# harp_load_cells_v1_1.net
KiCad netlist of a schematic drawn in EAGLE
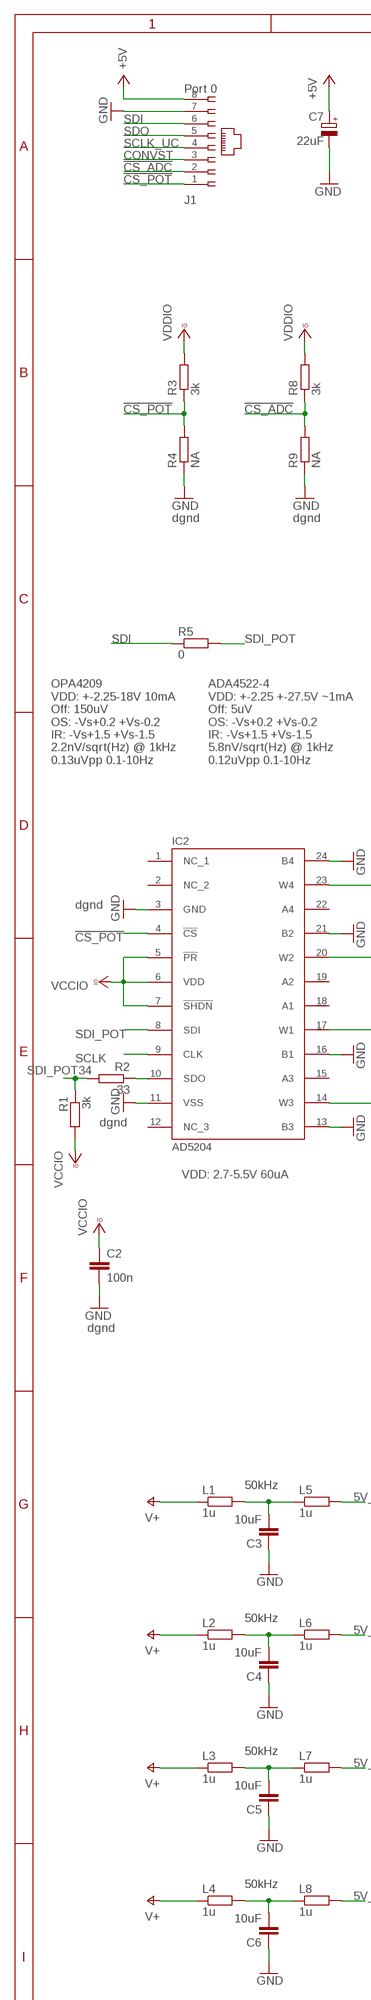
[diagram p0: schematic, sheet 1, part 1 of 2]
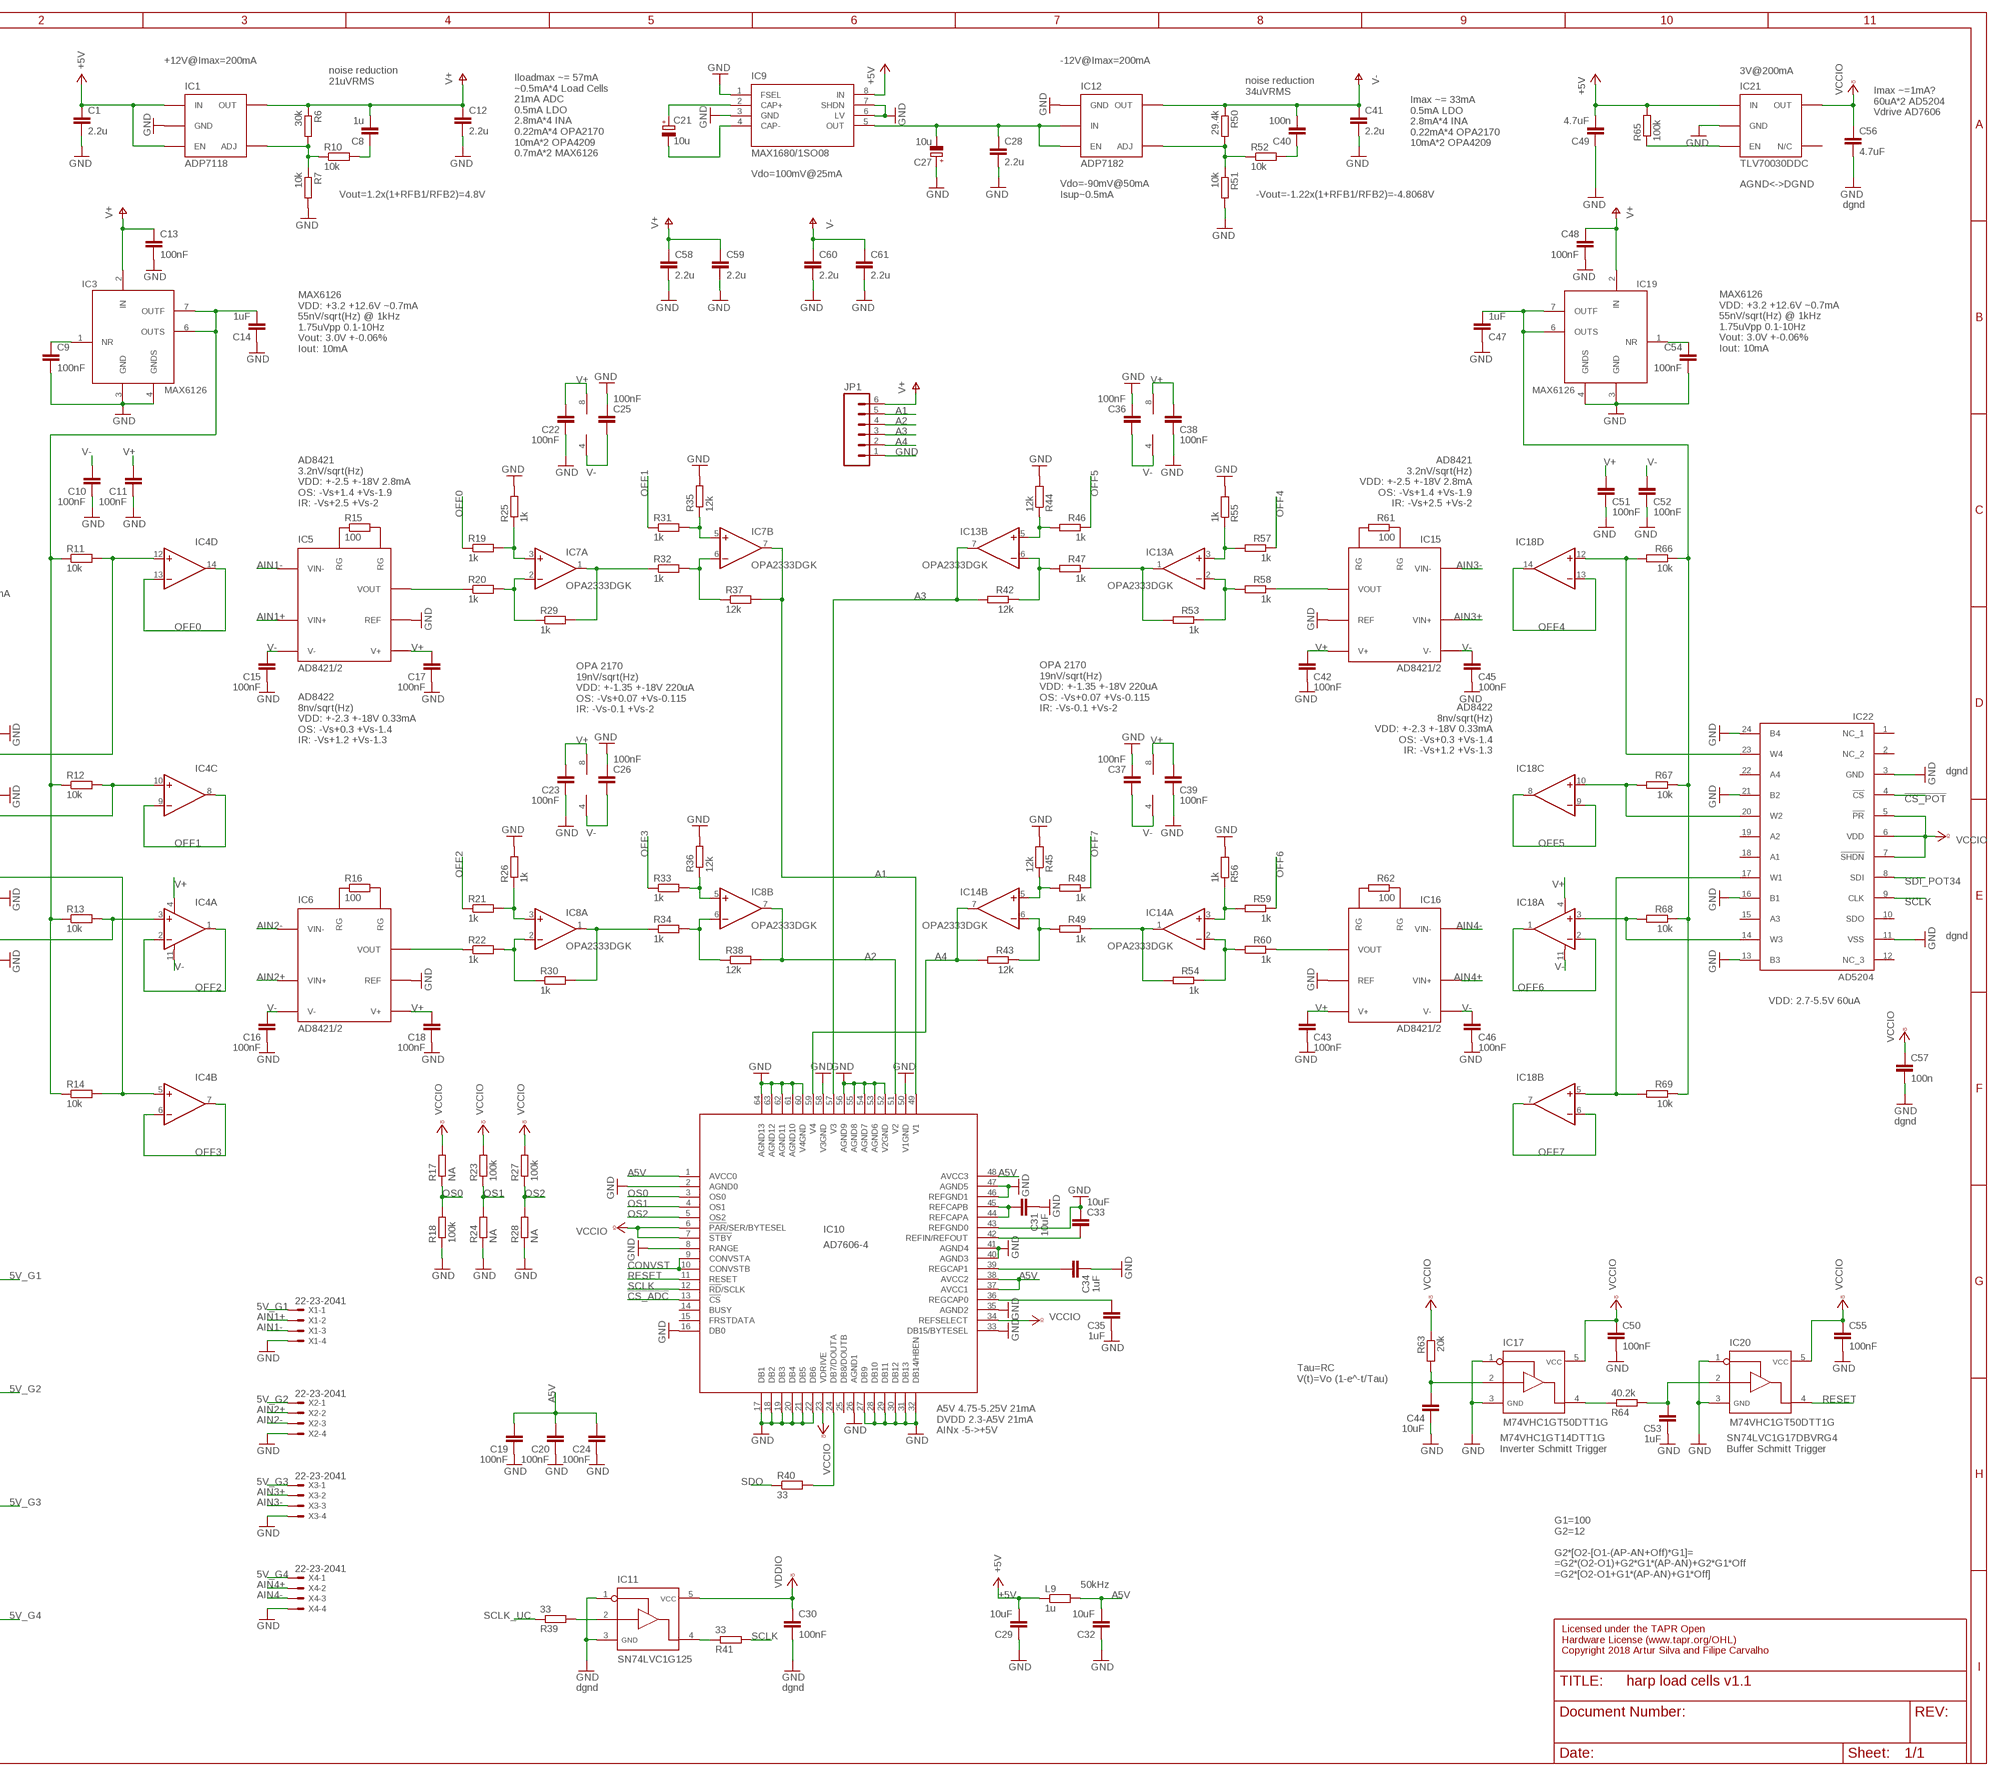
[diagram p1: schematic, sheet 1, part 2 of 2]

(export (version "E")
  (design (tool "Eeschema 10.0.6"))
  (components
    (comp (ref "C1")
      (value "2.2u")
      (footprint "eagle-import:C0603")
      (libsource (lib "eagle-import") (part "C-EUC0603"))
    )
    (comp (ref "C2")
      (value "100n")
      (footprint "eagle-import:C0402")
      (libsource (lib "eagle-import") (part "C-EUC0402"))
    )
    (comp (ref "C3")
      (value "10uF")
      (footprint "eagle-import:C0603")
      (libsource (lib "eagle-import") (part "C-EUC0603"))
    )
    (comp (ref "C4")
      (value "10uF")
      (footprint "eagle-import:C0603")
      (libsource (lib "eagle-import") (part "C-EUC0603"))
    )
    (comp (ref "C5")
      (value "10uF")
      (footprint "eagle-import:C0603")
      (libsource (lib "eagle-import") (part "C-EUC0603"))
    )
    (comp (ref "C6")
      (value "10uF")
      (footprint "eagle-import:C0603")
      (libsource (lib "eagle-import") (part "C-EUC0603"))
    )
    (comp (ref "C7")
      (value "22uF")
      (footprint "eagle-import:CAP_100UF_HAND")
      (libsource (lib "eagle-import") (part "CAP_100UFHAND"))
    )
    (comp (ref "C8")
      (value "1u")
      (footprint "eagle-import:C0402")
      (libsource (lib "eagle-import") (part "C-EUC0402"))
    )
    (comp (ref "C9")
      (value "100nF")
      (footprint "eagle-import:C0402")
      (libsource (lib "eagle-import") (part "C-EUC0402"))
    )
    (comp (ref "C10")
      (value "100nF")
      (footprint "eagle-import:C0402")
      (libsource (lib "eagle-import") (part "C-EUC0402"))
    )
    (comp (ref "C11")
      (value "100nF")
      (footprint "eagle-import:C0402")
      (libsource (lib "eagle-import") (part "C-EUC0402"))
    )
    (comp (ref "C12")
      (value "2.2u")
      (footprint "eagle-import:C0603")
      (libsource (lib "eagle-import") (part "C-EUC0603"))
    )
    (comp (ref "C13")
      (value "100nF")
      (footprint "eagle-import:C0402")
      (libsource (lib "eagle-import") (part "C-EUC0402"))
    )
    (comp (ref "C14")
      (value "1uF")
      (footprint "eagle-import:C0603")
      (libsource (lib "eagle-import") (part "C-EUC0603"))
    )
    (comp (ref "C15")
      (value "100nF")
      (footprint "eagle-import:C0402")
      (libsource (lib "eagle-import") (part "C-EUC0402"))
    )
    (comp (ref "C16")
      (value "100nF")
      (footprint "eagle-import:C0402")
      (libsource (lib "eagle-import") (part "C-EUC0402"))
    )
    (comp (ref "C17")
      (value "100nF")
      (footprint "eagle-import:C0402")
      (libsource (lib "eagle-import") (part "C-EUC0402"))
    )
    (comp (ref "C18")
      (value "100nF")
      (footprint "eagle-import:C0402")
      (libsource (lib "eagle-import") (part "C-EUC0402"))
    )
    (comp (ref "C19")
      (value "100nF")
      (footprint "eagle-import:C0402")
      (libsource (lib "eagle-import") (part "C-EUC0402"))
    )
    (comp (ref "C20")
      (value "100nF")
      (footprint "eagle-import:C0402")
      (libsource (lib "eagle-import") (part "C-EUC0402"))
    )
    (comp (ref "C21")
      (value "10u")
      (footprint "eagle-import:A_3216-18W")
      (libsource (lib "eagle-import") (part "CPOL-EUA/3216-18W"))
    )
    (comp (ref "C22")
      (value "100nF")
      (footprint "eagle-import:C0402")
      (libsource (lib "eagle-import") (part "C-EUC0402"))
    )
    (comp (ref "C23")
      (value "100nF")
      (footprint "eagle-import:C0402")
      (libsource (lib "eagle-import") (part "C-EUC0402"))
    )
    (comp (ref "C24")
      (value "100nF")
      (footprint "eagle-import:C0402")
      (libsource (lib "eagle-import") (part "C-EUC0402"))
    )
    (comp (ref "C25")
      (value "100nF")
      (footprint "eagle-import:C0402")
      (libsource (lib "eagle-import") (part "C-EUC0402"))
    )
    (comp (ref "C26")
      (value "100nF")
      (footprint "eagle-import:C0402")
      (libsource (lib "eagle-import") (part "C-EUC0402"))
    )
    (comp (ref "C27")
      (value "10u")
      (footprint "eagle-import:A_3216-18W")
      (libsource (lib "eagle-import") (part "CPOL-EUA/3216-18W"))
    )
    (comp (ref "C28")
      (value "2.2u")
      (footprint "eagle-import:C0603")
      (libsource (lib "eagle-import") (part "C-EUC0603"))
    )
    (comp (ref "C29")
      (value "10uF")
      (footprint "eagle-import:C0603")
      (libsource (lib "eagle-import") (part "C-EUC0603"))
    )
    (comp (ref "C30")
      (value "100nF")
      (footprint "eagle-import:C0402")
      (libsource (lib "eagle-import") (part "C-EUC0402"))
    )
    (comp (ref "C31")
      (value "10uF")
      (footprint "eagle-import:C0603")
      (libsource (lib "eagle-import") (part "C-EUC0603"))
    )
    (comp (ref "C32")
      (value "10uF")
      (footprint "eagle-import:C0603")
      (libsource (lib "eagle-import") (part "C-EUC0603"))
    )
    (comp (ref "C33")
      (value "10uF")
      (footprint "eagle-import:C0603")
      (libsource (lib "eagle-import") (part "C-EUC0603"))
    )
    (comp (ref "C34")
      (value "1uF")
      (footprint "eagle-import:C0402")
      (libsource (lib "eagle-import") (part "C-EUC0402"))
    )
    (comp (ref "C35")
      (value "1uF")
      (footprint "eagle-import:C0402")
      (libsource (lib "eagle-import") (part "C-EUC0402"))
    )
    (comp (ref "C36")
      (value "100nF")
      (footprint "eagle-import:C0402")
      (libsource (lib "eagle-import") (part "C-EUC0402"))
    )
    (comp (ref "C37")
      (value "100nF")
      (footprint "eagle-import:C0402")
      (libsource (lib "eagle-import") (part "C-EUC0402"))
    )
    (comp (ref "C38")
      (value "100nF")
      (footprint "eagle-import:C0402")
      (libsource (lib "eagle-import") (part "C-EUC0402"))
    )
    (comp (ref "C39")
      (value "100nF")
      (footprint "eagle-import:C0402")
      (libsource (lib "eagle-import") (part "C-EUC0402"))
    )
    (comp (ref "C40")
      (value "100n")
      (footprint "eagle-import:C0402")
      (libsource (lib "eagle-import") (part "C-EUC0402"))
    )
    (comp (ref "C41")
      (value "2.2u")
      (footprint "eagle-import:C0603")
      (libsource (lib "eagle-import") (part "C-EUC0603"))
    )
    (comp (ref "C42")
      (value "100nF")
      (footprint "eagle-import:C0402")
      (libsource (lib "eagle-import") (part "C-EUC0402"))
    )
    (comp (ref "C43")
      (value "100nF")
      (footprint "eagle-import:C0402")
      (libsource (lib "eagle-import") (part "C-EUC0402"))
    )
    (comp (ref "C44")
      (value "10uF")
      (footprint "eagle-import:C0603")
      (libsource (lib "eagle-import") (part "C-EUC0603"))
    )
    (comp (ref "C45")
      (value "100nF")
      (footprint "eagle-import:C0402")
      (libsource (lib "eagle-import") (part "C-EUC0402"))
    )
    (comp (ref "C46")
      (value "100nF")
      (footprint "eagle-import:C0402")
      (libsource (lib "eagle-import") (part "C-EUC0402"))
    )
    (comp (ref "C47")
      (value "1uF")
      (footprint "eagle-import:C0603")
      (libsource (lib "eagle-import") (part "C-EUC0603"))
    )
    (comp (ref "C48")
      (value "100nF")
      (footprint "eagle-import:C0402")
      (libsource (lib "eagle-import") (part "C-EUC0402"))
    )
    (comp (ref "C49")
      (value "4.7uF")
      (footprint "eagle-import:C0603")
      (libsource (lib "eagle-import") (part "C-EUC0603"))
    )
    (comp (ref "C50")
      (value "100nF")
      (footprint "eagle-import:C0402")
      (libsource (lib "eagle-import") (part "C-EUC0402"))
    )
    (comp (ref "C51")
      (value "100nF")
      (footprint "eagle-import:C0402")
      (libsource (lib "eagle-import") (part "C-EUC0402"))
    )
    (comp (ref "C52")
      (value "100nF")
      (footprint "eagle-import:C0402")
      (libsource (lib "eagle-import") (part "C-EUC0402"))
    )
    (comp (ref "C53")
      (value "1uF")
      (footprint "eagle-import:C0603")
      (libsource (lib "eagle-import") (part "C-EUC0603"))
    )
    (comp (ref "C54")
      (value "100nF")
      (footprint "eagle-import:C0402")
      (libsource (lib "eagle-import") (part "C-EUC0402"))
    )
    (comp (ref "C55")
      (value "100nF")
      (footprint "eagle-import:C0402")
      (libsource (lib "eagle-import") (part "C-EUC0402"))
    )
    (comp (ref "C56")
      (value "4.7uF")
      (footprint "eagle-import:C0603")
      (libsource (lib "eagle-import") (part "C-EUC0603"))
    )
    (comp (ref "C57")
      (value "100n")
      (footprint "eagle-import:C0402")
      (libsource (lib "eagle-import") (part "C-EUC0402"))
    )
    (comp (ref "C58")
      (value "2.2u")
      (footprint "eagle-import:C0603")
      (libsource (lib "eagle-import") (part "C-EUC0603"))
    )
    (comp (ref "C59")
      (value "2.2u")
      (footprint "eagle-import:C0603")
      (libsource (lib "eagle-import") (part "C-EUC0603"))
    )
    (comp (ref "C60")
      (value "2.2u")
      (footprint "eagle-import:C0603")
      (libsource (lib "eagle-import") (part "C-EUC0603"))
    )
    (comp (ref "C61")
      (value "2.2u")
      (footprint "eagle-import:C0603")
      (libsource (lib "eagle-import") (part "C-EUC0603"))
    )
    (comp (ref "IC1")
      (value "ADP7118")
      (footprint "eagle-import:TSOT23-5")
      (libsource (lib "eagle-import") (part "ADP7118"))
    )
    (comp (ref "IC2")
      (value "AD5204")
      (footprint "eagle-import:TSSOP-24")
      (libsource (lib "eagle-import") (part "AD5204"))
    )
    (comp (ref "IC3")
      (value "MAX6126")
      (footprint "eagle-import:SO08")
      (libsource (lib "eagle-import") (part "MAX6126"))
    )
    (comp (ref "IC4")
      (value "OPA4336T")
      (footprint "eagle-import:TSSOP-14")
      (libsource (lib "eagle-import") (part "OPA4336T"))
    )
    (comp (ref "IC5")
      (value "AD8421/2")
      (footprint "eagle-import:MSOP8")
      (libsource (lib "eagle-import") (part "AD8421/2"))
    )
    (comp (ref "IC6")
      (value "AD8421/2")
      (footprint "eagle-import:MSOP8")
      (libsource (lib "eagle-import") (part "AD8421/2"))
    )
    (comp (ref "IC7")
      (value "OPA2333DGK")
      (footprint "eagle-import:MSOP08")
      (libsource (lib "eagle-import") (part "OPA2333DGK"))
    )
    (comp (ref "IC8")
      (value "OPA2333DGK")
      (footprint "eagle-import:MSOP08")
      (libsource (lib "eagle-import") (part "OPA2333DGK"))
    )
    (comp (ref "IC9")
      (value "MAX1680/1SO08")
      (footprint "eagle-import:SO08")
      (libsource (lib "eagle-import") (part "MAX1680/1SO08"))
    )
    (comp (ref "IC10")
      (value "AD7606-4")
      (footprint "eagle-import:LQFP-64")
      (libsource (lib "eagle-import") (part "AD7606-4"))
    )
    (comp (ref "IC11")
      (value "SN74LVC1G125")
      (footprint "eagle-import:SOT23-5")
      (libsource (lib "eagle-import") (part "SN74LVC1G125"))
    )
    (comp (ref "IC12")
      (value "ADP7182")
      (footprint "eagle-import:TSOT23-5")
      (libsource (lib "eagle-import") (part "ADP7182"))
    )
    (comp (ref "IC13")
      (value "OPA2333DGK")
      (footprint "eagle-import:MSOP08")
      (libsource (lib "eagle-import") (part "OPA2333DGK"))
    )
    (comp (ref "IC14")
      (value "OPA2333DGK")
      (footprint "eagle-import:MSOP08")
      (libsource (lib "eagle-import") (part "OPA2333DGK"))
    )
    (comp (ref "IC15")
      (value "AD8421/2")
      (footprint "eagle-import:MSOP8")
      (libsource (lib "eagle-import") (part "AD8421/2"))
    )
    (comp (ref "IC16")
      (value "AD8421/2")
      (footprint "eagle-import:MSOP8")
      (libsource (lib "eagle-import") (part "AD8421/2"))
    )
    (comp (ref "IC17")
      (value "M74VHC1GT50DTT1G")
      (footprint "eagle-import:SOT23-5")
      (libsource (lib "eagle-import") (part "SN74LVC1G125"))
    )
    (comp (ref "IC18")
      (value "OPA4336T")
      (footprint "eagle-import:TSSOP-14")
      (libsource (lib "eagle-import") (part "OPA4336T"))
    )
    (comp (ref "IC19")
      (value "MAX6126")
      (footprint "eagle-import:SO08")
      (libsource (lib "eagle-import") (part "MAX6126"))
    )
    (comp (ref "IC20")
      (value "M74VHC1GT50DTT1G")
      (footprint "eagle-import:SOT23-5")
      (libsource (lib "eagle-import") (part "SN74LVC1G125"))
    )
    (comp (ref "IC21")
      (value "TLV70030DDC")
      (footprint "eagle-import:TSOT23-5")
      (libsource (lib "eagle-import") (part "TLV700XX"))
    )
    (comp (ref "IC22")
      (value "AD5204")
      (footprint "eagle-import:TSSOP-24")
      (libsource (lib "eagle-import") (part "AD5204"))
    )
    (comp (ref "J1")
      (value "Port 0")
      (footprint "eagle-import:520426-4")
      (libsource (lib "eagle-import") (part "520426-4"))
    )
    (comp (ref "JP1")
      (value "M06NO_SILK")
      (footprint "eagle-import:1X06_NO_SILK")
      (libsource (lib "eagle-import") (part "M06NO_SILK"))
    )
    (comp (ref "L1")
      (value "1u")
      (footprint "eagle-import:R0402")
      (libsource (lib "eagle-import") (part "R-EU_R0402"))
    )
    (comp (ref "L2")
      (value "1u")
      (footprint "eagle-import:R0402")
      (libsource (lib "eagle-import") (part "R-EU_R0402"))
    )
    (comp (ref "L3")
      (value "1u")
      (footprint "eagle-import:R0402")
      (libsource (lib "eagle-import") (part "R-EU_R0402"))
    )
    (comp (ref "L4")
      (value "1u")
      (footprint "eagle-import:R0402")
      (libsource (lib "eagle-import") (part "R-EU_R0402"))
    )
    (comp (ref "L5")
      (value "1u")
      (footprint "eagle-import:R0402")
      (libsource (lib "eagle-import") (part "R-EU_R0402"))
    )
    (comp (ref "L6")
      (value "1u")
      (footprint "eagle-import:R0402")
      (libsource (lib "eagle-import") (part "R-EU_R0402"))
    )
    (comp (ref "L7")
      (value "1u")
      (footprint "eagle-import:R0402")
      (libsource (lib "eagle-import") (part "R-EU_R0402"))
    )
    (comp (ref "L8")
      (value "1u")
      (footprint "eagle-import:R0402")
      (libsource (lib "eagle-import") (part "R-EU_R0402"))
    )
    (comp (ref "L9")
      (value "1u")
      (footprint "eagle-import:R0402")
      (libsource (lib "eagle-import") (part "R-EU_R0402"))
    )
    (comp (ref "R1")
      (value "3k")
      (footprint "eagle-import:R0402")
      (libsource (lib "eagle-import") (part "R-EU_R0402"))
    )
    (comp (ref "R2")
      (value "33")
      (footprint "eagle-import:R0402")
      (libsource (lib "eagle-import") (part "R-EU_R0402"))
    )
    (comp (ref "R3")
      (value "3k")
      (footprint "eagle-import:R0402")
      (libsource (lib "eagle-import") (part "R-EU_R0402"))
    )
    (comp (ref "R4")
      (value "NA")
      (footprint "eagle-import:R0402")
      (libsource (lib "eagle-import") (part "R-EU_R0402"))
    )
    (comp (ref "R5")
      (value "0")
      (footprint "eagle-import:R0402")
      (libsource (lib "eagle-import") (part "R-EU_R0402"))
    )
    (comp (ref "R6")
      (value "30k")
      (footprint "eagle-import:R0402")
      (libsource (lib "eagle-import") (part "R-EU_R0402"))
    )
    (comp (ref "R7")
      (value "10k")
      (footprint "eagle-import:R0402")
      (libsource (lib "eagle-import") (part "R-EU_R0402"))
    )
    (comp (ref "R8")
      (value "3k")
      (footprint "eagle-import:R0402")
      (libsource (lib "eagle-import") (part "R-EU_R0402"))
    )
    (comp (ref "R9")
      (value "NA")
      (footprint "eagle-import:R0402")
      (libsource (lib "eagle-import") (part "R-EU_R0402"))
    )
    (comp (ref "R10")
      (value "10k")
      (footprint "eagle-import:R0402")
      (libsource (lib "eagle-import") (part "R-EU_R0402"))
    )
    (comp (ref "R11")
      (value "10k")
      (footprint "eagle-import:R0402")
      (libsource (lib "eagle-import") (part "R-EU_R0402"))
    )
    (comp (ref "R12")
      (value "10k")
      (footprint "eagle-import:R0402")
      (libsource (lib "eagle-import") (part "R-EU_R0402"))
    )
    (comp (ref "R13")
      (value "10k")
      (footprint "eagle-import:R0402")
      (libsource (lib "eagle-import") (part "R-EU_R0402"))
    )
    (comp (ref "R14")
      (value "10k")
      (footprint "eagle-import:R0402")
      (libsource (lib "eagle-import") (part "R-EU_R0402"))
    )
    (comp (ref "R15")
      (value "100")
      (footprint "eagle-import:R0402")
      (libsource (lib "eagle-import") (part "R-EU_R0402"))
    )
    (comp (ref "R16")
      (value "100")
      (footprint "eagle-import:R0402")
      (libsource (lib "eagle-import") (part "R-EU_R0402"))
    )
    (comp (ref "R17")
      (value "NA")
      (footprint "eagle-import:R0402")
      (libsource (lib "eagle-import") (part "R-EU_R0402"))
    )
    (comp (ref "R18")
      (value "100k")
      (footprint "eagle-import:R0402")
      (libsource (lib "eagle-import") (part "R-EU_R0402"))
    )
    (comp (ref "R19")
      (value "1k")
      (footprint "eagle-import:R0402")
      (libsource (lib "eagle-import") (part "R-EU_R0402"))
    )
    (comp (ref "R20")
      (value "1k")
      (footprint "eagle-import:R0402")
      (libsource (lib "eagle-import") (part "R-EU_R0402"))
    )
    (comp (ref "R21")
      (value "1k")
      (footprint "eagle-import:R0402")
      (libsource (lib "eagle-import") (part "R-EU_R0402"))
    )
    (comp (ref "R22")
      (value "1k")
      (footprint "eagle-import:R0402")
      (libsource (lib "eagle-import") (part "R-EU_R0402"))
    )
    (comp (ref "R23")
      (value "100k")
      (footprint "eagle-import:R0402")
      (libsource (lib "eagle-import") (part "R-EU_R0402"))
    )
    (comp (ref "R24")
      (value "NA")
      (footprint "eagle-import:R0402")
      (libsource (lib "eagle-import") (part "R-EU_R0402"))
    )
    (comp (ref "R25")
      (value "1k")
      (footprint "eagle-import:R0402")
      (libsource (lib "eagle-import") (part "R-EU_R0402"))
    )
    (comp (ref "R26")
      (value "1k")
      (footprint "eagle-import:R0402")
      (libsource (lib "eagle-import") (part "R-EU_R0402"))
    )
    (comp (ref "R27")
      (value "100k")
      (footprint "eagle-import:R0402")
      (libsource (lib "eagle-import") (part "R-EU_R0402"))
    )
    (comp (ref "R28")
      (value "NA")
      (footprint "eagle-import:R0402")
      (libsource (lib "eagle-import") (part "R-EU_R0402"))
    )
    (comp (ref "R29")
      (value "1k")
      (footprint "eagle-import:R0402")
      (libsource (lib "eagle-import") (part "R-EU_R0402"))
    )
    (comp (ref "R30")
      (value "1k")
      (footprint "eagle-import:R0402")
      (libsource (lib "eagle-import") (part "R-EU_R0402"))
    )
    (comp (ref "R31")
      (value "1k")
      (footprint "eagle-import:R0402")
      (libsource (lib "eagle-import") (part "R-EU_R0402"))
    )
    (comp (ref "R32")
      (value "1k")
      (footprint "eagle-import:R0402")
      (libsource (lib "eagle-import") (part "R-EU_R0402"))
    )
    (comp (ref "R33")
      (value "1k")
      (footprint "eagle-import:R0402")
      (libsource (lib "eagle-import") (part "R-EU_R0402"))
    )
    (comp (ref "R34")
      (value "1k")
      (footprint "eagle-import:R0402")
      (libsource (lib "eagle-import") (part "R-EU_R0402"))
    )
    (comp (ref "R35")
      (value "12k")
      (footprint "eagle-import:R0402")
      (libsource (lib "eagle-import") (part "R-EU_R0402"))
    )
    (comp (ref "R36")
      (value "12k")
      (footprint "eagle-import:R0402")
      (libsource (lib "eagle-import") (part "R-EU_R0402"))
    )
    (comp (ref "R37")
      (value "12k")
      (footprint "eagle-import:R0402")
      (libsource (lib "eagle-import") (part "R-EU_R0402"))
    )
    (comp (ref "R38")
      (value "12k")
      (footprint "eagle-import:R0402")
      (libsource (lib "eagle-import") (part "R-EU_R0402"))
    )
    (comp (ref "R39")
      (value "33")
      (footprint "eagle-import:R0402")
      (libsource (lib "eagle-import") (part "R-EU_R0402"))
    )
    (comp (ref "R40")
      (value "33")
      (footprint "eagle-import:R0402")
      (libsource (lib "eagle-import") (part "R-EU_R0402"))
    )
    (comp (ref "R41")
      (value "33")
      (footprint "eagle-import:R0402")
      (libsource (lib "eagle-import") (part "R-EU_R0402"))
    )
    (comp (ref "R42")
      (value "12k")
      (footprint "eagle-import:R0402")
      (libsource (lib "eagle-import") (part "R-EU_R0402"))
    )
    (comp (ref "R43")
      (value "12k")
      (footprint "eagle-import:R0402")
      (libsource (lib "eagle-import") (part "R-EU_R0402"))
    )
    (comp (ref "R44")
      (value "12k")
      (footprint "eagle-import:R0402")
      (libsource (lib "eagle-import") (part "R-EU_R0402"))
    )
    (comp (ref "R45")
      (value "12k")
      (footprint "eagle-import:R0402")
      (libsource (lib "eagle-import") (part "R-EU_R0402"))
    )
    (comp (ref "R46")
      (value "1k")
      (footprint "eagle-import:R0402")
      (libsource (lib "eagle-import") (part "R-EU_R0402"))
    )
    (comp (ref "R47")
      (value "1k")
      (footprint "eagle-import:R0402")
      (libsource (lib "eagle-import") (part "R-EU_R0402"))
    )
    (comp (ref "R48")
      (value "1k")
      (footprint "eagle-import:R0402")
      (libsource (lib "eagle-import") (part "R-EU_R0402"))
    )
    (comp (ref "R49")
      (value "1k")
      (footprint "eagle-import:R0402")
      (libsource (lib "eagle-import") (part "R-EU_R0402"))
    )
    (comp (ref "R50")
      (value "29.4k")
      (footprint "eagle-import:R0402")
      (libsource (lib "eagle-import") (part "R-EU_R0402"))
    )
    (comp (ref "R51")
      (value "10k")
      (footprint "eagle-import:R0402")
      (libsource (lib "eagle-import") (part "R-EU_R0402"))
    )
    (comp (ref "R52")
      (value "10k")
      (footprint "eagle-import:R0402")
      (libsource (lib "eagle-import") (part "R-EU_R0402"))
    )
    (comp (ref "R53")
      (value "1k")
      (footprint "eagle-import:R0402")
      (libsource (lib "eagle-import") (part "R-EU_R0402"))
    )
    (comp (ref "R54")
      (value "1k")
      (footprint "eagle-import:R0402")
      (libsource (lib "eagle-import") (part "R-EU_R0402"))
    )
    (comp (ref "R55")
      (value "1k")
      (footprint "eagle-import:R0402")
      (libsource (lib "eagle-import") (part "R-EU_R0402"))
    )
    (comp (ref "R56")
      (value "1k")
      (footprint "eagle-import:R0402")
      (libsource (lib "eagle-import") (part "R-EU_R0402"))
    )
    (comp (ref "R57")
      (value "1k")
      (footprint "eagle-import:R0402")
      (libsource (lib "eagle-import") (part "R-EU_R0402"))
    )
    (comp (ref "R58")
      (value "1k")
      (footprint "eagle-import:R0402")
      (libsource (lib "eagle-import") (part "R-EU_R0402"))
    )
    (comp (ref "R59")
      (value "1k")
      (footprint "eagle-import:R0402")
      (libsource (lib "eagle-import") (part "R-EU_R0402"))
    )
    (comp (ref "R60")
      (value "1k")
      (footprint "eagle-import:R0402")
      (libsource (lib "eagle-import") (part "R-EU_R0402"))
    )
    (comp (ref "R61")
      (value "100")
      (footprint "eagle-import:R0402")
      (libsource (lib "eagle-import") (part "R-EU_R0402"))
    )
    (comp (ref "R62")
      (value "100")
      (footprint "eagle-import:R0402")
      (libsource (lib "eagle-import") (part "R-EU_R0402"))
    )
    (comp (ref "R63")
      (value "20k")
      (footprint "eagle-import:R0402")
      (libsource (lib "eagle-import") (part "R-EU_R0402"))
    )
    (comp (ref "R64")
      (value "40.2k")
      (footprint "eagle-import:R0402")
      (libsource (lib "eagle-import") (part "R-EU_R0402"))
    )
    (comp (ref "R65")
      (value "100k")
      (footprint "eagle-import:R0402")
      (libsource (lib "eagle-import") (part "R-EU_R0402"))
    )
    (comp (ref "R66")
      (value "10k")
      (footprint "eagle-import:R0402")
      (libsource (lib "eagle-import") (part "R-EU_R0402"))
    )
    (comp (ref "R67")
      (value "10k")
      (footprint "eagle-import:R0402")
      (libsource (lib "eagle-import") (part "R-EU_R0402"))
    )
    (comp (ref "R68")
      (value "10k")
      (footprint "eagle-import:R0402")
      (libsource (lib "eagle-import") (part "R-EU_R0402"))
    )
    (comp (ref "R69")
      (value "10k")
      (footprint "eagle-import:R0402")
      (libsource (lib "eagle-import") (part "R-EU_R0402"))
    )
    (comp (ref "X1")
      (value "22-23-2041")
      (footprint "eagle-import:22-23-2041")
      (fields (field (name "MF") "MOLEX"))
      (libsource (lib "eagle-import") (part "22-23-2041"))
    )
    (comp (ref "X2")
      (value "22-23-2041")
      (footprint "eagle-import:22-23-2041")
      (fields (field (name "MF") "MOLEX"))
      (libsource (lib "eagle-import") (part "22-23-2041"))
    )
    (comp (ref "X3")
      (value "22-23-2041")
      (footprint "eagle-import:22-23-2041")
      (fields (field (name "MF") "MOLEX"))
      (libsource (lib "eagle-import") (part "22-23-2041"))
    )
    (comp (ref "X4")
      (value "22-23-2041")
      (footprint "eagle-import:22-23-2041")
      (fields (field (name "MF") "MOLEX"))
      (libsource (lib "eagle-import") (part "22-23-2041"))
    )
  )
  (nets
    (net (code "1") (name "+5V") (class "Default")
      (node (ref "C1") (pin "1") (pinfunction "1_1") (pintype "passive"))
      (node (ref "C29") (pin "2") (pinfunction "2_2") (pintype "passive"))
      (node (ref "C49") (pin "2") (pinfunction "2_2") (pintype "passive"))
      (node (ref "C7") (pin "+") (pinfunction "+_+") (pintype "passive"))
      (node (ref "IC1") (pin "1") (pinfunction "IN_1") (pintype "bidirectional"))
      (node (ref "IC1") (pin "3") (pinfunction "EN_3") (pintype "bidirectional"))
      (node (ref "IC21") (pin "1") (pinfunction "IN_1") (pintype "bidirectional"))
      (node (ref "IC9") (pin "8") (pinfunction "IN_8") (pintype "bidirectional"))
      (node (ref "J1") (pin "8") (pinfunction "8_8") (pintype "passive"))
      (node (ref "L9") (pin "1") (pinfunction "1_1") (pintype "passive"))
      (node (ref "R65") (pin "2") (pinfunction "2_2") (pintype "passive"))
    )
    (net (code "2") (name "/5V_G1") (class "Default")
      (node (ref "L5") (pin "2") (pinfunction "2_2") (pintype "passive"))
      (node (ref "X1") (pin "1") (pinfunction "S_1") (pintype "passive"))
    )
    (net (code "3") (name "/5V_G2") (class "Default")
      (node (ref "L6") (pin "2") (pinfunction "2_2") (pintype "passive"))
      (node (ref "X2") (pin "1") (pinfunction "S_1") (pintype "passive"))
    )
    (net (code "4") (name "/5V_G3") (class "Default")
      (node (ref "L7") (pin "2") (pinfunction "2_2") (pintype "passive"))
      (node (ref "X3") (pin "1") (pinfunction "S_1") (pintype "passive"))
    )
    (net (code "5") (name "/5V_G4") (class "Default")
      (node (ref "L8") (pin "2") (pinfunction "2_2") (pintype "passive"))
      (node (ref "X4") (pin "1") (pinfunction "S_1") (pintype "passive"))
    )
    (net (code "6") (name "/A1") (class "Default")
      (node (ref "IC10") (pin "49") (pinfunction "V1_49") (pintype "bidirectional"))
      (node (ref "IC7") (pin "7") (pinfunction "OUT_7") (pintype "output"))
      (node (ref "JP1") (pin "5") (pinfunction "5_5") (pintype "passive"))
      (node (ref "R37") (pin "2") (pinfunction "2_2") (pintype "passive"))
    )
    (net (code "7") (name "/A2") (class "Default")
      (node (ref "IC10") (pin "51") (pinfunction "V2_51") (pintype "bidirectional"))
      (node (ref "IC8") (pin "7") (pinfunction "OUT_7") (pintype "output"))
      (node (ref "JP1") (pin "4") (pinfunction "4_4") (pintype "passive"))
      (node (ref "R38") (pin "2") (pinfunction "2_2") (pintype "passive"))
    )
    (net (code "8") (name "/A3") (class "Default")
      (node (ref "IC10") (pin "57") (pinfunction "V3_57") (pintype "bidirectional"))
      (node (ref "IC13") (pin "7") (pinfunction "OUT_7") (pintype "output"))
      (node (ref "JP1") (pin "3") (pinfunction "3_3") (pintype "passive"))
      (node (ref "R42") (pin "2") (pinfunction "2_2") (pintype "passive"))
    )
    (net (code "9") (name "/A4") (class "Default")
      (node (ref "IC10") (pin "59") (pinfunction "V4_59") (pintype "bidirectional"))
      (node (ref "IC14") (pin "7") (pinfunction "OUT_7") (pintype "output"))
      (node (ref "JP1") (pin "2") (pinfunction "2_2") (pintype "passive"))
      (node (ref "R43") (pin "2") (pinfunction "2_2") (pintype "passive"))
    )
    (net (code "10") (name "/A5V") (class "Default")
      (node (ref "C19") (pin "2") (pinfunction "2_2") (pintype "passive"))
      (node (ref "C20") (pin "2") (pinfunction "2_2") (pintype "passive"))
      (node (ref "C24") (pin "2") (pinfunction "2_2") (pintype "passive"))
      (node (ref "C32") (pin "2") (pinfunction "2_2") (pintype "passive"))
      (node (ref "IC10") (pin "1") (pinfunction "AVCC0_1") (pintype "bidirectional"))
      (node (ref "IC10") (pin "37") (pinfunction "AVCC1_37") (pintype "bidirectional"))
      (node (ref "IC10") (pin "38") (pinfunction "AVCC2_38") (pintype "bidirectional"))
      (node (ref "IC10") (pin "48") (pinfunction "AVCC3_48") (pintype "bidirectional"))
      (node (ref "L9") (pin "2") (pinfunction "2_2") (pintype "passive"))
    )
    (net (code "11") (name "/AIN1+") (class "Default")
      (node (ref "IC5") (pin "P$4") (pinfunction "VIN+_P$4") (pintype "bidirectional"))
      (node (ref "X1") (pin "2") (pinfunction "S_2") (pintype "passive"))
    )
    (net (code "12") (name "/AIN1-") (class "Default")
      (node (ref "IC5") (pin "P$1") (pinfunction "VIN-_P$1") (pintype "bidirectional"))
      (node (ref "X1") (pin "3") (pinfunction "S_3") (pintype "passive"))
    )
    (net (code "13") (name "/AIN2+") (class "Default")
      (node (ref "IC6") (pin "P$4") (pinfunction "VIN+_P$4") (pintype "bidirectional"))
      (node (ref "X2") (pin "2") (pinfunction "S_2") (pintype "passive"))
    )
    (net (code "14") (name "/AIN2-") (class "Default")
      (node (ref "IC6") (pin "P$1") (pinfunction "VIN-_P$1") (pintype "bidirectional"))
      (node (ref "X2") (pin "3") (pinfunction "S_3") (pintype "passive"))
    )
    (net (code "15") (name "/AIN3+") (class "Default")
      (node (ref "IC15") (pin "P$4") (pinfunction "VIN+_P$4") (pintype "bidirectional"))
      (node (ref "X3") (pin "2") (pinfunction "S_2") (pintype "passive"))
    )
    (net (code "16") (name "/AIN3-") (class "Default")
      (node (ref "IC15") (pin "P$1") (pinfunction "VIN-_P$1") (pintype "bidirectional"))
      (node (ref "X3") (pin "3") (pinfunction "S_3") (pintype "passive"))
    )
    (net (code "17") (name "/AIN4+") (class "Default")
      (node (ref "IC16") (pin "P$4") (pinfunction "VIN+_P$4") (pintype "bidirectional"))
      (node (ref "X4") (pin "2") (pinfunction "S_2") (pintype "passive"))
    )
    (net (code "18") (name "/AIN4-") (class "Default")
      (node (ref "IC16") (pin "P$1") (pinfunction "VIN-_P$1") (pintype "bidirectional"))
      (node (ref "X4") (pin "3") (pinfunction "S_3") (pintype "passive"))
    )
    (net (code "19") (name "/CONVST") (class "Default")
      (node (ref "IC10") (pin "10") (pinfunction "CONVSTB_10") (pintype "bidirectional"))
      (node (ref "IC10") (pin "9") (pinfunction "CONVSTA_9") (pintype "bidirectional"))
      (node (ref "J1") (pin "3") (pinfunction "3_3") (pintype "passive"))
    )
    (net (code "20") (name "/OFF0") (class "Default")
      (node (ref "IC4") (pin "13") (pinfunction "-IN_13") (pintype "input"))
      (node (ref "IC4") (pin "14") (pinfunction "OUT_14") (pintype "output"))
      (node (ref "R19") (pin "1") (pinfunction "1_1") (pintype "passive"))
    )
    (net (code "21") (name "/OFF1") (class "Default")
      (node (ref "IC4") (pin "8") (pinfunction "OUT_8") (pintype "output"))
      (node (ref "IC4") (pin "9") (pinfunction "-IN_9") (pintype "input"))
      (node (ref "R31") (pin "1") (pinfunction "1_1") (pintype "passive"))
    )
    (net (code "22") (name "/OFF2") (class "Default")
      (node (ref "IC4") (pin "1") (pinfunction "OUT_1") (pintype "output"))
      (node (ref "IC4") (pin "2") (pinfunction "-IN_2") (pintype "input"))
      (node (ref "R21") (pin "1") (pinfunction "1_1") (pintype "passive"))
    )
    (net (code "23") (name "/OFF3") (class "Default")
      (node (ref "IC4") (pin "6") (pinfunction "-IN_6") (pintype "input"))
      (node (ref "IC4") (pin "7") (pinfunction "OUT_7") (pintype "output"))
      (node (ref "R33") (pin "1") (pinfunction "1_1") (pintype "passive"))
    )
    (net (code "24") (name "/OFF4") (class "Default")
      (node (ref "IC18") (pin "13") (pinfunction "-IN_13") (pintype "input"))
      (node (ref "IC18") (pin "14") (pinfunction "OUT_14") (pintype "output"))
      (node (ref "R57") (pin "1") (pinfunction "1_1") (pintype "passive"))
    )
    (net (code "25") (name "/OFF5") (class "Default")
      (node (ref "IC18") (pin "8") (pinfunction "OUT_8") (pintype "output"))
      (node (ref "IC18") (pin "9") (pinfunction "-IN_9") (pintype "input"))
      (node (ref "R46") (pin "1") (pinfunction "1_1") (pintype "passive"))
    )
    (net (code "26") (name "/OFF6") (class "Default")
      (node (ref "IC18") (pin "1") (pinfunction "OUT_1") (pintype "output"))
      (node (ref "IC18") (pin "2") (pinfunction "-IN_2") (pintype "input"))
      (node (ref "R59") (pin "1") (pinfunction "1_1") (pintype "passive"))
    )
    (net (code "27") (name "/OFF7") (class "Default")
      (node (ref "IC18") (pin "6") (pinfunction "-IN_6") (pintype "input"))
      (node (ref "IC18") (pin "7") (pinfunction "OUT_7") (pintype "output"))
      (node (ref "R48") (pin "1") (pinfunction "1_1") (pintype "passive"))
    )
    (net (code "28") (name "/OS0") (class "Default")
      (node (ref "IC10") (pin "3") (pinfunction "OS0_3") (pintype "bidirectional"))
      (node (ref "R17") (pin "1") (pinfunction "1_1") (pintype "passive"))
      (node (ref "R18") (pin "2") (pinfunction "2_2") (pintype "passive"))
    )
    (net (code "29") (name "/OS1") (class "Default")
      (node (ref "IC10") (pin "4") (pinfunction "OS1_4") (pintype "bidirectional"))
      (node (ref "R23") (pin "1") (pinfunction "1_1") (pintype "passive"))
      (node (ref "R24") (pin "2") (pinfunction "2_2") (pintype "passive"))
    )
    (net (code "30") (name "/OS2") (class "Default")
      (node (ref "IC10") (pin "5") (pinfunction "OS2_5") (pintype "bidirectional"))
      (node (ref "R27") (pin "1") (pinfunction "1_1") (pintype "passive"))
      (node (ref "R28") (pin "2") (pinfunction "2_2") (pintype "passive"))
    )
    (net (code "31") (name "/RESET") (class "Default")
      (node (ref "IC10") (pin "11") (pinfunction "RESET_11") (pintype "bidirectional"))
      (node (ref "IC20") (pin "4") (pinfunction "P$4_4") (pintype "bidirectional"))
    )
    (net (code "32") (name "/SCLK") (class "Default")
      (node (ref "IC10") (pin "12") (pinfunction "~{RD}/SCLK_12") (pintype "bidirectional"))
      (node (ref "IC2") (pin "9") (pinfunction "CLK_9") (pintype "bidirectional"))
      (node (ref "IC22") (pin "9") (pinfunction "CLK_9") (pintype "bidirectional"))
      (node (ref "R41") (pin "2") (pinfunction "2_2") (pintype "passive"))
    )
    (net (code "33") (name "/SCLK_UC") (class "Default")
      (node (ref "J1") (pin "4") (pinfunction "4_4") (pintype "passive"))
      (node (ref "R39") (pin "1") (pinfunction "1_1") (pintype "passive"))
    )
    (net (code "34") (name "/SDI") (class "Default")
      (node (ref "J1") (pin "6") (pinfunction "6_6") (pintype "passive"))
      (node (ref "R5") (pin "1") (pinfunction "1_1") (pintype "passive"))
    )
    (net (code "35") (name "/SDI_POT") (class "Default")
      (node (ref "IC2") (pin "8") (pinfunction "SDI_8") (pintype "bidirectional"))
      (node (ref "R5") (pin "2") (pinfunction "2_2") (pintype "passive"))
    )
    (net (code "36") (name "/SDI_POT34") (class "Default")
      (node (ref "IC22") (pin "8") (pinfunction "SDI_8") (pintype "bidirectional"))
      (node (ref "R1") (pin "1") (pinfunction "1_1") (pintype "passive"))
      (node (ref "R2") (pin "2") (pinfunction "2_2") (pintype "passive"))
    )
    (net (code "37") (name "/SDO") (class "Default")
      (node (ref "J1") (pin "5") (pinfunction "5_5") (pintype "passive"))
      (node (ref "R40") (pin "1") (pinfunction "1_1") (pintype "passive"))
    )
    (net (code "38") (name "/~{CS_ADC}") (class "Default")
      (node (ref "IC10") (pin "13") (pinfunction "~{CS}_13") (pintype "input"))
      (node (ref "J1") (pin "2") (pinfunction "2_2") (pintype "passive"))
      (node (ref "R8") (pin "1") (pinfunction "1_1") (pintype "passive"))
      (node (ref "R9") (pin "2") (pinfunction "2_2") (pintype "passive"))
    )
    (net (code "39") (name "/~{CS_POT}") (class "Default")
      (node (ref "IC2") (pin "4") (pinfunction "~{CS}_4") (pintype "bidirectional"))
      (node (ref "IC22") (pin "4") (pinfunction "~{CS}_4") (pintype "bidirectional"))
      (node (ref "J1") (pin "1") (pinfunction "1_1") (pintype "passive"))
      (node (ref "R3") (pin "1") (pinfunction "1_1") (pintype "passive"))
      (node (ref "R4") (pin "2") (pinfunction "2_2") (pintype "passive"))
    )
    (net (code "40") (name "GND") (class "Default")
      (node (ref "C1") (pin "2") (pinfunction "2_2") (pintype "passive"))
      (node (ref "C10") (pin "1") (pinfunction "1_1") (pintype "passive"))
      (node (ref "C11") (pin "1") (pinfunction "1_1") (pintype "passive"))
      (node (ref "C12") (pin "2") (pinfunction "2_2") (pintype "passive"))
      (node (ref "C13") (pin "2") (pinfunction "2_2") (pintype "passive"))
      (node (ref "C14") (pin "1") (pinfunction "1_1") (pintype "passive"))
      (node (ref "C15") (pin "1") (pinfunction "1_1") (pintype "passive"))
      (node (ref "C16") (pin "1") (pinfunction "1_1") (pintype "passive"))
      (node (ref "C17") (pin "1") (pinfunction "1_1") (pintype "passive"))
      (node (ref "C18") (pin "1") (pinfunction "1_1") (pintype "passive"))
      (node (ref "C19") (pin "1") (pinfunction "1_1") (pintype "passive"))
      (node (ref "C2") (pin "2") (pinfunction "2_2") (pintype "passive"))
      (node (ref "C20") (pin "1") (pinfunction "1_1") (pintype "passive"))
      (node (ref "C22") (pin "1") (pinfunction "1_1") (pintype "passive"))
      (node (ref "C23") (pin "1") (pinfunction "1_1") (pintype "passive"))
      (node (ref "C24") (pin "1") (pinfunction "1_1") (pintype "passive"))
      (node (ref "C25") (pin "1") (pinfunction "1_1") (pintype "passive"))
      (node (ref "C26") (pin "1") (pinfunction "1_1") (pintype "passive"))
      (node (ref "C27") (pin "+") (pinfunction "+_+") (pintype "passive"))
      (node (ref "C28") (pin "2") (pinfunction "2_2") (pintype "passive"))
      (node (ref "C29") (pin "1") (pinfunction "1_1") (pintype "passive"))
      (node (ref "C3") (pin "1") (pinfunction "1_1") (pintype "passive"))
      (node (ref "C30") (pin "2") (pinfunction "2_2") (pintype "passive"))
      (node (ref "C31") (pin "1") (pinfunction "1_1") (pintype "passive"))
      (node (ref "C32") (pin "1") (pinfunction "1_1") (pintype "passive"))
      (node (ref "C33") (pin "1") (pinfunction "1_1") (pintype "passive"))
      (node (ref "C34") (pin "1") (pinfunction "1_1") (pintype "passive"))
      (node (ref "C35") (pin "1") (pinfunction "1_1") (pintype "passive"))
      (node (ref "C36") (pin "1") (pinfunction "1_1") (pintype "passive"))
      (node (ref "C37") (pin "1") (pinfunction "1_1") (pintype "passive"))
      (node (ref "C38") (pin "1") (pinfunction "1_1") (pintype "passive"))
      (node (ref "C39") (pin "1") (pinfunction "1_1") (pintype "passive"))
      (node (ref "C4") (pin "1") (pinfunction "1_1") (pintype "passive"))
      (node (ref "C41") (pin "2") (pinfunction "2_2") (pintype "passive"))
      (node (ref "C42") (pin "1") (pinfunction "1_1") (pintype "passive"))
      (node (ref "C43") (pin "1") (pinfunction "1_1") (pintype "passive"))
      (node (ref "C44") (pin "1") (pinfunction "1_1") (pintype "passive"))
      (node (ref "C45") (pin "1") (pinfunction "1_1") (pintype "passive"))
      (node (ref "C46") (pin "1") (pinfunction "1_1") (pintype "passive"))
      (node (ref "C47") (pin "1") (pinfunction "1_1") (pintype "passive"))
      (node (ref "C48") (pin "2") (pinfunction "2_2") (pintype "passive"))
      (node (ref "C49") (pin "1") (pinfunction "1_1") (pintype "passive"))
      (node (ref "C5") (pin "1") (pinfunction "1_1") (pintype "passive"))
      (node (ref "C50") (pin "2") (pinfunction "2_2") (pintype "passive"))
      (node (ref "C51") (pin "1") (pinfunction "1_1") (pintype "passive"))
      (node (ref "C52") (pin "1") (pinfunction "1_1") (pintype "passive"))
      (node (ref "C53") (pin "1") (pinfunction "1_1") (pintype "passive"))
      (node (ref "C54") (pin "2") (pinfunction "2_2") (pintype "passive"))
      (node (ref "C55") (pin "2") (pinfunction "2_2") (pintype "passive"))
      (node (ref "C56") (pin "2") (pinfunction "2_2") (pintype "passive"))
      (node (ref "C57") (pin "2") (pinfunction "2_2") (pintype "passive"))
      (node (ref "C58") (pin "2") (pinfunction "2_2") (pintype "passive"))
      (node (ref "C59") (pin "2") (pinfunction "2_2") (pintype "passive"))
      (node (ref "C6") (pin "1") (pinfunction "1_1") (pintype "passive"))
      (node (ref "C60") (pin "2") (pinfunction "2_2") (pintype "passive"))
      (node (ref "C61") (pin "2") (pinfunction "2_2") (pintype "passive"))
      (node (ref "C7") (pin "-") (pinfunction "-_-") (pintype "passive"))
      (node (ref "C9") (pin "2") (pinfunction "2_2") (pintype "passive"))
      (node (ref "IC1") (pin "2") (pinfunction "GND_2") (pintype "bidirectional"))
      (node (ref "IC10") (pin "16") (pinfunction "DB0_16") (pintype "bidirectional"))
      (node (ref "IC10") (pin "17") (pinfunction "DB1_17") (pintype "bidirectional"))
      (node (ref "IC10") (pin "18") (pinfunction "DB2_18") (pintype "bidirectional"))
      (node (ref "IC10") (pin "19") (pinfunction "DB3_19") (pintype "bidirectional"))
      (node (ref "IC10") (pin "2") (pinfunction "AGND0_2") (pintype "bidirectional"))
      (node (ref "IC10") (pin "20") (pinfunction "DB4_20") (pintype "bidirectional"))
      (node (ref "IC10") (pin "21") (pinfunction "DB5_21") (pintype "bidirectional"))
      (node (ref "IC10") (pin "22") (pinfunction "DB6_22") (pintype "bidirectional"))
      (node (ref "IC10") (pin "26") (pinfunction "AGND1_26") (pintype "bidirectional"))
      (node (ref "IC10") (pin "27") (pinfunction "DB9_27") (pintype "bidirectional"))
      (node (ref "IC10") (pin "28") (pinfunction "DB10_28") (pintype "bidirectional"))
      (node (ref "IC10") (pin "29") (pinfunction "DB11_29") (pintype "input"))
      (node (ref "IC10") (pin "30") (pinfunction "DB12_30") (pintype "bidirectional"))
      (node (ref "IC10") (pin "31") (pinfunction "DB13_31") (pintype "bidirectional"))
      (node (ref "IC10") (pin "32") (pinfunction "DB14/HBEN_32") (pintype "bidirectional"))
      (node (ref "IC10") (pin "33") (pinfunction "DB15/BYTESEL_33") (pintype "bidirectional"))
      (node (ref "IC10") (pin "35") (pinfunction "AGND2_35") (pintype "bidirectional"))
      (node (ref "IC10") (pin "40") (pinfunction "AGND3_40") (pintype "bidirectional"))
      (node (ref "IC10") (pin "41") (pinfunction "AGND4_41") (pintype "bidirectional"))
      (node (ref "IC10") (pin "43") (pinfunction "REFGND0_43") (pintype "bidirectional"))
      (node (ref "IC10") (pin "46") (pinfunction "REFGND1_46") (pintype "bidirectional"))
      (node (ref "IC10") (pin "47") (pinfunction "AGND5_47") (pintype "bidirectional"))
      (node (ref "IC10") (pin "50") (pinfunction "V1GND_50") (pintype "bidirectional"))
      (node (ref "IC10") (pin "52") (pinfunction "V2GND_52") (pintype "bidirectional"))
      (node (ref "IC10") (pin "53") (pinfunction "AGND6_53") (pintype "bidirectional"))
      (node (ref "IC10") (pin "54") (pinfunction "AGND7_54") (pintype "bidirectional"))
      (node (ref "IC10") (pin "55") (pinfunction "AGND8_55") (pintype "bidirectional"))
      (node (ref "IC10") (pin "56") (pinfunction "AGND9_56") (pintype "bidirectional"))
      (node (ref "IC10") (pin "58") (pinfunction "V3GND_58") (pintype "bidirectional"))
      (node (ref "IC10") (pin "60") (pinfunction "V4GND_60") (pintype "bidirectional"))
      (node (ref "IC10") (pin "61") (pinfunction "AGND10_61") (pintype "bidirectional"))
      (node (ref "IC10") (pin "62") (pinfunction "AGND11_62") (pintype "bidirectional"))
      (node (ref "IC10") (pin "63") (pinfunction "AGND12_63") (pintype "bidirectional"))
      (node (ref "IC10") (pin "64") (pinfunction "AGND13_64") (pintype "bidirectional"))
      (node (ref "IC10") (pin "8") (pinfunction "RANGE_8") (pintype "bidirectional"))
      (node (ref "IC11") (pin "1") (pinfunction "P$1_1") (pintype "bidirectional"))
      (node (ref "IC11") (pin "3") (pinfunction "P$3_3") (pintype "bidirectional"))
      (node (ref "IC12") (pin "1") (pinfunction "GND_1") (pintype "bidirectional"))
      (node (ref "IC15") (pin "P$6") (pinfunction "REF_P$6") (pintype "bidirectional"))
      (node (ref "IC16") (pin "P$6") (pinfunction "REF_P$6") (pintype "bidirectional"))
      (node (ref "IC17") (pin "1") (pinfunction "P$1_1") (pintype "bidirectional"))
      (node (ref "IC17") (pin "3") (pinfunction "P$3_3") (pintype "bidirectional"))
      (node (ref "IC19") (pin "3") (pinfunction "GND_3") (pintype "power_in"))
      (node (ref "IC19") (pin "4") (pinfunction "GNDS_4") (pintype "power_in"))
      (node (ref "IC2") (pin "11") (pinfunction "VSS_11") (pintype "power_in"))
      (node (ref "IC2") (pin "13") (pinfunction "B3_13") (pintype "bidirectional"))
      (node (ref "IC2") (pin "16") (pinfunction "B1_16") (pintype "bidirectional"))
      (node (ref "IC2") (pin "21") (pinfunction "B2_21") (pintype "bidirectional"))
      (node (ref "IC2") (pin "24") (pinfunction "B4_24") (pintype "bidirectional"))
      (node (ref "IC2") (pin "3") (pinfunction "GND_3") (pintype "power_in"))
      (node (ref "IC20") (pin "1") (pinfunction "P$1_1") (pintype "bidirectional"))
      (node (ref "IC20") (pin "3") (pinfunction "P$3_3") (pintype "bidirectional"))
      (node (ref "IC21") (pin "2") (pinfunction "GND_2") (pintype "bidirectional"))
      (node (ref "IC22") (pin "11") (pinfunction "VSS_11") (pintype "power_in"))
      (node (ref "IC22") (pin "13") (pinfunction "B3_13") (pintype "bidirectional"))
      (node (ref "IC22") (pin "16") (pinfunction "B1_16") (pintype "bidirectional"))
      (node (ref "IC22") (pin "21") (pinfunction "B2_21") (pintype "bidirectional"))
      (node (ref "IC22") (pin "24") (pinfunction "B4_24") (pintype "bidirectional"))
      (node (ref "IC22") (pin "3") (pinfunction "GND_3") (pintype "power_in"))
      (node (ref "IC3") (pin "3") (pinfunction "GND_3") (pintype "power_in"))
      (node (ref "IC3") (pin "4") (pinfunction "GNDS_4") (pintype "power_in"))
      (node (ref "IC5") (pin "P$6") (pinfunction "REF_P$6") (pintype "bidirectional"))
      (node (ref "IC6") (pin "P$6") (pinfunction "REF_P$6") (pintype "bidirectional"))
      (node (ref "IC9") (pin "1") (pinfunction "FSEL_1") (pintype "bidirectional"))
      (node (ref "IC9") (pin "3") (pinfunction "GND_3") (pintype "bidirectional"))
      (node (ref "IC9") (pin "6") (pinfunction "LV_6") (pintype "bidirectional"))
      (node (ref "IC9") (pin "7") (pinfunction "SHDN_7") (pintype "bidirectional"))
      (node (ref "J1") (pin "7") (pinfunction "7_7") (pintype "passive"))
      (node (ref "JP1") (pin "1") (pinfunction "1_1") (pintype "passive"))
      (node (ref "R18") (pin "1") (pinfunction "1_1") (pintype "passive"))
      (node (ref "R24") (pin "1") (pinfunction "1_1") (pintype "passive"))
      (node (ref "R25") (pin "2") (pinfunction "2_2") (pintype "passive"))
      (node (ref "R26") (pin "2") (pinfunction "2_2") (pintype "passive"))
      (node (ref "R28") (pin "1") (pinfunction "1_1") (pintype "passive"))
      (node (ref "R35") (pin "2") (pinfunction "2_2") (pintype "passive"))
      (node (ref "R36") (pin "2") (pinfunction "2_2") (pintype "passive"))
      (node (ref "R4") (pin "1") (pinfunction "1_1") (pintype "passive"))
      (node (ref "R44") (pin "2") (pinfunction "2_2") (pintype "passive"))
      (node (ref "R45") (pin "2") (pinfunction "2_2") (pintype "passive"))
      (node (ref "R51") (pin "2") (pinfunction "2_2") (pintype "passive"))
      (node (ref "R55") (pin "2") (pinfunction "2_2") (pintype "passive"))
      (node (ref "R56") (pin "2") (pinfunction "2_2") (pintype "passive"))
      (node (ref "R7") (pin "2") (pinfunction "2_2") (pintype "passive"))
      (node (ref "R9") (pin "1") (pinfunction "1_1") (pintype "passive"))
      (node (ref "X1") (pin "4") (pinfunction "S_4") (pintype "passive"))
      (node (ref "X2") (pin "4") (pinfunction "S_4") (pintype "passive"))
      (node (ref "X3") (pin "4") (pinfunction "S_4") (pintype "passive"))
      (node (ref "X4") (pin "4") (pinfunction "S_4") (pintype "passive"))
    )
    (net (code "41") (name "Net-(C3-Pad2)") (class "Default")
      (node (ref "C3") (pin "2") (pinfunction "2_2") (pintype "passive"))
      (node (ref "L1") (pin "2") (pinfunction "2_2") (pintype "passive"))
      (node (ref "L5") (pin "1") (pinfunction "1_1") (pintype "passive"))
    )
    (net (code "42") (name "Net-(C4-Pad2)") (class "Default")
      (node (ref "C4") (pin "2") (pinfunction "2_2") (pintype "passive"))
      (node (ref "L2") (pin "2") (pinfunction "2_2") (pintype "passive"))
      (node (ref "L6") (pin "1") (pinfunction "1_1") (pintype "passive"))
    )
    (net (code "43") (name "Net-(C5-Pad2)") (class "Default")
      (node (ref "C5") (pin "2") (pinfunction "2_2") (pintype "passive"))
      (node (ref "L3") (pin "2") (pinfunction "2_2") (pintype "passive"))
      (node (ref "L7") (pin "1") (pinfunction "1_1") (pintype "passive"))
    )
    (net (code "44") (name "Net-(C6-Pad2)") (class "Default")
      (node (ref "C6") (pin "2") (pinfunction "2_2") (pintype "passive"))
      (node (ref "L4") (pin "2") (pinfunction "2_2") (pintype "passive"))
      (node (ref "L8") (pin "1") (pinfunction "1_1") (pintype "passive"))
    )
    (net (code "45") (name "Net-(C8-Pad1)") (class "Default")
      (node (ref "C8") (pin "1") (pinfunction "1_1") (pintype "passive"))
      (node (ref "R10") (pin "2") (pinfunction "2_2") (pintype "passive"))
    )
    (net (code "46") (name "Net-(C40-Pad1)") (class "Default")
      (node (ref "C40") (pin "1") (pinfunction "1_1") (pintype "passive"))
      (node (ref "R52") (pin "2") (pinfunction "2_2") (pintype "passive"))
    )
    (net (code "47") (name "Net-(IC1-ADJ)") (class "Default")
      (node (ref "IC1") (pin "4") (pinfunction "ADJ_4") (pintype "bidirectional"))
      (node (ref "R10") (pin "1") (pinfunction "1_1") (pintype "passive"))
      (node (ref "R6") (pin "2") (pinfunction "2_2") (pintype "passive"))
      (node (ref "R7") (pin "1") (pinfunction "1_1") (pintype "passive"))
    )
    (net (code "48") (name "Net-(IC2-SDO)") (class "Default")
      (node (ref "IC2") (pin "10") (pinfunction "SDO_10") (pintype "bidirectional"))
      (node (ref "R2") (pin "1") (pinfunction "1_1") (pintype "passive"))
    )
    (net (code "49") (name "Net-(IC2-W1)") (class "Default")
      (node (ref "IC2") (pin "17") (pinfunction "W1_17") (pintype "bidirectional"))
      (node (ref "IC4") (pin "5") (pinfunction "+IN_5") (pintype "input"))
      (node (ref "R14") (pin "2") (pinfunction "2_2") (pintype "passive"))
    )
    (net (code "50") (name "Net-(IC2-W2)") (class "Default")
      (node (ref "IC2") (pin "20") (pinfunction "W2_20") (pintype "bidirectional"))
      (node (ref "IC4") (pin "10") (pinfunction "+IN_10") (pintype "input"))
      (node (ref "R12") (pin "2") (pinfunction "2_2") (pintype "passive"))
    )
    (net (code "51") (name "Net-(IC2-W3)") (class "Default")
      (node (ref "IC2") (pin "14") (pinfunction "W3_14") (pintype "bidirectional"))
      (node (ref "IC4") (pin "3") (pinfunction "+IN_3") (pintype "input"))
      (node (ref "R13") (pin "2") (pinfunction "2_2") (pintype "passive"))
    )
    (net (code "52") (name "Net-(IC2-W4)") (class "Default")
      (node (ref "IC2") (pin "23") (pinfunction "W4_23") (pintype "bidirectional"))
      (node (ref "IC4") (pin "12") (pinfunction "+IN_12") (pintype "input"))
      (node (ref "R11") (pin "2") (pinfunction "2_2") (pintype "passive"))
    )
    (net (code "53") (name "Net-(IC3-NR)") (class "Default")
      (node (ref "C9") (pin "1") (pinfunction "1_1") (pintype "passive"))
      (node (ref "IC3") (pin "1") (pinfunction "NR_1") (pintype "bidirectional"))
    )
    (net (code "54") (name "Net-(IC3-OUTF)") (class "Default")
      (node (ref "C14") (pin "2") (pinfunction "2_2") (pintype "passive"))
      (node (ref "IC3") (pin "6") (pinfunction "OUTS_6") (pintype "bidirectional"))
      (node (ref "IC3") (pin "7") (pinfunction "OUTF_7") (pintype "bidirectional"))
      (node (ref "R11") (pin "1") (pinfunction "1_1") (pintype "passive"))
      (node (ref "R12") (pin "1") (pinfunction "1_1") (pintype "passive"))
      (node (ref "R13") (pin "1") (pinfunction "1_1") (pintype "passive"))
      (node (ref "R14") (pin "1") (pinfunction "1_1") (pintype "passive"))
    )
    (net (code "55") (name "Net-(IC5-RG-PadP$2)") (class "Default")
      (node (ref "IC5") (pin "P$2") (pinfunction "RG_P$2") (pintype "bidirectional"))
      (node (ref "R15") (pin "2") (pinfunction "2_2") (pintype "passive"))
    )
    (net (code "56") (name "Net-(IC5-RG-PadP$3)") (class "Default")
      (node (ref "IC5") (pin "P$3") (pinfunction "RG_P$3") (pintype "bidirectional"))
      (node (ref "R15") (pin "1") (pinfunction "1_1") (pintype "passive"))
    )
    (net (code "57") (name "Net-(IC5-VOUT)") (class "Default")
      (node (ref "IC5") (pin "P$7") (pinfunction "VOUT_P$7") (pintype "bidirectional"))
      (node (ref "R20") (pin "1") (pinfunction "1_1") (pintype "passive"))
    )
    (net (code "58") (name "Net-(IC6-RG-PadP$2)") (class "Default")
      (node (ref "IC6") (pin "P$2") (pinfunction "RG_P$2") (pintype "bidirectional"))
      (node (ref "R16") (pin "2") (pinfunction "2_2") (pintype "passive"))
    )
    (net (code "59") (name "Net-(IC6-RG-PadP$3)") (class "Default")
      (node (ref "IC6") (pin "P$3") (pinfunction "RG_P$3") (pintype "bidirectional"))
      (node (ref "R16") (pin "1") (pinfunction "1_1") (pintype "passive"))
    )
    (net (code "60") (name "Net-(IC6-VOUT)") (class "Default")
      (node (ref "IC6") (pin "P$7") (pinfunction "VOUT_P$7") (pintype "bidirectional"))
      (node (ref "R22") (pin "1") (pinfunction "1_1") (pintype "passive"))
    )
    (net (code "61") (name "Net-(IC7A-+IN)") (class "Default")
      (node (ref "IC7") (pin "3") (pinfunction "+IN_3") (pintype "input"))
      (node (ref "R19") (pin "2") (pinfunction "2_2") (pintype "passive"))
      (node (ref "R25") (pin "1") (pinfunction "1_1") (pintype "passive"))
    )
    (net (code "62") (name "Net-(IC7A--IN)") (class "Default")
      (node (ref "IC7") (pin "2") (pinfunction "-IN_2") (pintype "input"))
      (node (ref "R20") (pin "2") (pinfunction "2_2") (pintype "passive"))
      (node (ref "R29") (pin "1") (pinfunction "1_1") (pintype "passive"))
    )
    (net (code "63") (name "Net-(IC7A-OUT)") (class "Default")
      (node (ref "IC7") (pin "1") (pinfunction "OUT_1") (pintype "output"))
      (node (ref "R29") (pin "2") (pinfunction "2_2") (pintype "passive"))
      (node (ref "R32") (pin "1") (pinfunction "1_1") (pintype "passive"))
    )
    (net (code "64") (name "Net-(IC7B-+IN)") (class "Default")
      (node (ref "IC7") (pin "5") (pinfunction "+IN_5") (pintype "input"))
      (node (ref "R31") (pin "2") (pinfunction "2_2") (pintype "passive"))
      (node (ref "R35") (pin "1") (pinfunction "1_1") (pintype "passive"))
    )
    (net (code "65") (name "Net-(IC7B--IN)") (class "Default")
      (node (ref "IC7") (pin "6") (pinfunction "-IN_6") (pintype "input"))
      (node (ref "R32") (pin "2") (pinfunction "2_2") (pintype "passive"))
      (node (ref "R37") (pin "1") (pinfunction "1_1") (pintype "passive"))
    )
    (net (code "66") (name "Net-(IC8A-+IN)") (class "Default")
      (node (ref "IC8") (pin "3") (pinfunction "+IN_3") (pintype "input"))
      (node (ref "R21") (pin "2") (pinfunction "2_2") (pintype "passive"))
      (node (ref "R26") (pin "1") (pinfunction "1_1") (pintype "passive"))
    )
    (net (code "67") (name "Net-(IC8A--IN)") (class "Default")
      (node (ref "IC8") (pin "2") (pinfunction "-IN_2") (pintype "input"))
      (node (ref "R22") (pin "2") (pinfunction "2_2") (pintype "passive"))
      (node (ref "R30") (pin "1") (pinfunction "1_1") (pintype "passive"))
    )
    (net (code "68") (name "Net-(IC8A-OUT)") (class "Default")
      (node (ref "IC8") (pin "1") (pinfunction "OUT_1") (pintype "output"))
      (node (ref "R30") (pin "2") (pinfunction "2_2") (pintype "passive"))
      (node (ref "R34") (pin "1") (pinfunction "1_1") (pintype "passive"))
    )
    (net (code "69") (name "Net-(IC8B-+IN)") (class "Default")
      (node (ref "IC8") (pin "5") (pinfunction "+IN_5") (pintype "input"))
      (node (ref "R33") (pin "2") (pinfunction "2_2") (pintype "passive"))
      (node (ref "R36") (pin "1") (pinfunction "1_1") (pintype "passive"))
    )
    (net (code "70") (name "Net-(IC8B--IN)") (class "Default")
      (node (ref "IC8") (pin "6") (pinfunction "-IN_6") (pintype "input"))
      (node (ref "R34") (pin "2") (pinfunction "2_2") (pintype "passive"))
      (node (ref "R38") (pin "1") (pinfunction "1_1") (pintype "passive"))
    )
    (net (code "71") (name "Net-(IC9-CAP+)") (class "Default")
      (node (ref "C21") (pin "+") (pinfunction "+_+") (pintype "passive"))
      (node (ref "IC9") (pin "2") (pinfunction "CAP+_2") (pintype "bidirectional"))
    )
    (net (code "72") (name "Net-(IC9-CAP-)") (class "Default")
      (node (ref "C21") (pin "-") (pinfunction "-_-") (pintype "passive"))
      (node (ref "IC9") (pin "4") (pinfunction "CAP-_4") (pintype "bidirectional"))
    )
    (net (code "73") (name "Net-(IC10-DB7{slash}DOUTA)") (class "Default")
      (node (ref "IC10") (pin "24") (pinfunction "DB7/DOUTA_24") (pintype "bidirectional"))
      (node (ref "R40") (pin "2") (pinfunction "2_2") (pintype "passive"))
    )
    (net (code "74") (name "Net-(IC10-REFCAPA)") (class "Default")
      (node (ref "C31") (pin "2") (pinfunction "2_2") (pintype "passive"))
      (node (ref "IC10") (pin "44") (pinfunction "REFCAPA_44") (pintype "bidirectional"))
      (node (ref "IC10") (pin "45") (pinfunction "REFCAPB_45") (pintype "bidirectional"))
    )
    (net (code "75") (name "Net-(IC10-REFIN{slash}REFOUT)") (class "Default")
      (node (ref "C33") (pin "2") (pinfunction "2_2") (pintype "passive"))
      (node (ref "IC10") (pin "42") (pinfunction "REFIN/REFOUT_42") (pintype "input"))
    )
    (net (code "76") (name "Net-(IC10-REGCAP0)") (class "Default")
      (node (ref "C35") (pin "2") (pinfunction "2_2") (pintype "passive"))
      (node (ref "IC10") (pin "36") (pinfunction "REGCAP0_36") (pintype "bidirectional"))
    )
    (net (code "77") (name "Net-(IC10-REGCAP1)") (class "Default")
      (node (ref "C34") (pin "2") (pinfunction "2_2") (pintype "passive"))
      (node (ref "IC10") (pin "39") (pinfunction "REGCAP1_39") (pintype "bidirectional"))
    )
    (net (code "78") (name "Net-(IC11-P$2)") (class "Default")
      (node (ref "IC11") (pin "2") (pinfunction "P$2_2") (pintype "bidirectional"))
      (node (ref "R39") (pin "2") (pinfunction "2_2") (pintype "passive"))
    )
    (net (code "79") (name "Net-(IC11-P$4)") (class "Default")
      (node (ref "IC11") (pin "4") (pinfunction "P$4_4") (pintype "bidirectional"))
      (node (ref "R41") (pin "1") (pinfunction "1_1") (pintype "passive"))
    )
    (net (code "80") (name "Net-(IC12-ADJ)") (class "Default")
      (node (ref "IC12") (pin "4") (pinfunction "ADJ_4") (pintype "bidirectional"))
      (node (ref "R50") (pin "2") (pinfunction "2_2") (pintype "passive"))
      (node (ref "R51") (pin "1") (pinfunction "1_1") (pintype "passive"))
      (node (ref "R52") (pin "1") (pinfunction "1_1") (pintype "passive"))
    )
    (net (code "81") (name "Net-(IC12-EN)") (class "Default")
      (node (ref "C27") (pin "-") (pinfunction "-_-") (pintype "passive"))
      (node (ref "C28") (pin "1") (pinfunction "1_1") (pintype "passive"))
      (node (ref "IC12") (pin "2") (pinfunction "IN_2") (pintype "bidirectional"))
      (node (ref "IC12") (pin "3") (pinfunction "EN_3") (pintype "bidirectional"))
      (node (ref "IC9") (pin "5") (pinfunction "OUT_5") (pintype "bidirectional"))
    )
    (net (code "82") (name "Net-(IC13A-+IN)") (class "Default")
      (node (ref "IC13") (pin "3") (pinfunction "+IN_3") (pintype "input"))
      (node (ref "R55") (pin "1") (pinfunction "1_1") (pintype "passive"))
      (node (ref "R57") (pin "2") (pinfunction "2_2") (pintype "passive"))
    )
    (net (code "83") (name "Net-(IC13A--IN)") (class "Default")
      (node (ref "IC13") (pin "2") (pinfunction "-IN_2") (pintype "input"))
      (node (ref "R53") (pin "1") (pinfunction "1_1") (pintype "passive"))
      (node (ref "R58") (pin "2") (pinfunction "2_2") (pintype "passive"))
    )
    (net (code "84") (name "Net-(IC13A-OUT)") (class "Default")
      (node (ref "IC13") (pin "1") (pinfunction "OUT_1") (pintype "output"))
      (node (ref "R47") (pin "1") (pinfunction "1_1") (pintype "passive"))
      (node (ref "R53") (pin "2") (pinfunction "2_2") (pintype "passive"))
    )
    (net (code "85") (name "Net-(IC13B-+IN)") (class "Default")
      (node (ref "IC13") (pin "5") (pinfunction "+IN_5") (pintype "input"))
      (node (ref "R44") (pin "1") (pinfunction "1_1") (pintype "passive"))
      (node (ref "R46") (pin "2") (pinfunction "2_2") (pintype "passive"))
    )
    (net (code "86") (name "Net-(IC13B--IN)") (class "Default")
      (node (ref "IC13") (pin "6") (pinfunction "-IN_6") (pintype "input"))
      (node (ref "R42") (pin "1") (pinfunction "1_1") (pintype "passive"))
      (node (ref "R47") (pin "2") (pinfunction "2_2") (pintype "passive"))
    )
    (net (code "87") (name "Net-(IC14A-+IN)") (class "Default")
      (node (ref "IC14") (pin "3") (pinfunction "+IN_3") (pintype "input"))
      (node (ref "R56") (pin "1") (pinfunction "1_1") (pintype "passive"))
      (node (ref "R59") (pin "2") (pinfunction "2_2") (pintype "passive"))
    )
    (net (code "88") (name "Net-(IC14A--IN)") (class "Default")
      (node (ref "IC14") (pin "2") (pinfunction "-IN_2") (pintype "input"))
      (node (ref "R54") (pin "1") (pinfunction "1_1") (pintype "passive"))
      (node (ref "R60") (pin "2") (pinfunction "2_2") (pintype "passive"))
    )
    (net (code "89") (name "Net-(IC14A-OUT)") (class "Default")
      (node (ref "IC14") (pin "1") (pinfunction "OUT_1") (pintype "output"))
      (node (ref "R49") (pin "1") (pinfunction "1_1") (pintype "passive"))
      (node (ref "R54") (pin "2") (pinfunction "2_2") (pintype "passive"))
    )
    (net (code "90") (name "Net-(IC14B-+IN)") (class "Default")
      (node (ref "IC14") (pin "5") (pinfunction "+IN_5") (pintype "input"))
      (node (ref "R45") (pin "1") (pinfunction "1_1") (pintype "passive"))
      (node (ref "R48") (pin "2") (pinfunction "2_2") (pintype "passive"))
    )
    (net (code "91") (name "Net-(IC14B--IN)") (class "Default")
      (node (ref "IC14") (pin "6") (pinfunction "-IN_6") (pintype "input"))
      (node (ref "R43") (pin "1") (pinfunction "1_1") (pintype "passive"))
      (node (ref "R49") (pin "2") (pinfunction "2_2") (pintype "passive"))
    )
    (net (code "92") (name "Net-(IC15-RG-PadP$2)") (class "Default")
      (node (ref "IC15") (pin "P$2") (pinfunction "RG_P$2") (pintype "bidirectional"))
      (node (ref "R61") (pin "2") (pinfunction "2_2") (pintype "passive"))
    )
    (net (code "93") (name "Net-(IC15-RG-PadP$3)") (class "Default")
      (node (ref "IC15") (pin "P$3") (pinfunction "RG_P$3") (pintype "bidirectional"))
      (node (ref "R61") (pin "1") (pinfunction "1_1") (pintype "passive"))
    )
    (net (code "94") (name "Net-(IC15-VOUT)") (class "Default")
      (node (ref "IC15") (pin "P$7") (pinfunction "VOUT_P$7") (pintype "bidirectional"))
      (node (ref "R58") (pin "1") (pinfunction "1_1") (pintype "passive"))
    )
    (net (code "95") (name "Net-(IC16-RG-PadP$2)") (class "Default")
      (node (ref "IC16") (pin "P$2") (pinfunction "RG_P$2") (pintype "bidirectional"))
      (node (ref "R62") (pin "2") (pinfunction "2_2") (pintype "passive"))
    )
    (net (code "96") (name "Net-(IC16-RG-PadP$3)") (class "Default")
      (node (ref "IC16") (pin "P$3") (pinfunction "RG_P$3") (pintype "bidirectional"))
      (node (ref "R62") (pin "1") (pinfunction "1_1") (pintype "passive"))
    )
    (net (code "97") (name "Net-(IC16-VOUT)") (class "Default")
      (node (ref "IC16") (pin "P$7") (pinfunction "VOUT_P$7") (pintype "bidirectional"))
      (node (ref "R60") (pin "1") (pinfunction "1_1") (pintype "passive"))
    )
    (net (code "98") (name "Net-(IC17-P$2)") (class "Default")
      (node (ref "C44") (pin "2") (pinfunction "2_2") (pintype "passive"))
      (node (ref "IC17") (pin "2") (pinfunction "P$2_2") (pintype "bidirectional"))
      (node (ref "R63") (pin "2") (pinfunction "2_2") (pintype "passive"))
    )
    (net (code "99") (name "Net-(IC17-P$4)") (class "Default")
      (node (ref "IC17") (pin "4") (pinfunction "P$4_4") (pintype "bidirectional"))
      (node (ref "R64") (pin "1") (pinfunction "1_1") (pintype "passive"))
    )
    (net (code "100") (name "Net-(IC18A-+IN)") (class "Default")
      (node (ref "IC18") (pin "3") (pinfunction "+IN_3") (pintype "input"))
      (node (ref "IC22") (pin "14") (pinfunction "W3_14") (pintype "bidirectional"))
      (node (ref "R68") (pin "2") (pinfunction "2_2") (pintype "passive"))
    )
    (net (code "101") (name "Net-(IC18B-+IN)") (class "Default")
      (node (ref "IC18") (pin "5") (pinfunction "+IN_5") (pintype "input"))
      (node (ref "IC22") (pin "17") (pinfunction "W1_17") (pintype "bidirectional"))
      (node (ref "R69") (pin "2") (pinfunction "2_2") (pintype "passive"))
    )
    (net (code "102") (name "Net-(IC18C-+IN)") (class "Default")
      (node (ref "IC18") (pin "10") (pinfunction "+IN_10") (pintype "input"))
      (node (ref "IC22") (pin "20") (pinfunction "W2_20") (pintype "bidirectional"))
      (node (ref "R67") (pin "2") (pinfunction "2_2") (pintype "passive"))
    )
    (net (code "103") (name "Net-(IC18D-+IN)") (class "Default")
      (node (ref "IC18") (pin "12") (pinfunction "+IN_12") (pintype "input"))
      (node (ref "IC22") (pin "23") (pinfunction "W4_23") (pintype "bidirectional"))
      (node (ref "R66") (pin "2") (pinfunction "2_2") (pintype "passive"))
    )
    (net (code "104") (name "Net-(IC19-NR)") (class "Default")
      (node (ref "C54") (pin "1") (pinfunction "1_1") (pintype "passive"))
      (node (ref "IC19") (pin "1") (pinfunction "NR_1") (pintype "bidirectional"))
    )
    (net (code "105") (name "Net-(IC19-OUTF)") (class "Default")
      (node (ref "C47") (pin "2") (pinfunction "2_2") (pintype "passive"))
      (node (ref "IC19") (pin "6") (pinfunction "OUTS_6") (pintype "bidirectional"))
      (node (ref "IC19") (pin "7") (pinfunction "OUTF_7") (pintype "bidirectional"))
      (node (ref "R66") (pin "1") (pinfunction "1_1") (pintype "passive"))
      (node (ref "R67") (pin "1") (pinfunction "1_1") (pintype "passive"))
      (node (ref "R68") (pin "1") (pinfunction "1_1") (pintype "passive"))
      (node (ref "R69") (pin "1") (pinfunction "1_1") (pintype "passive"))
    )
    (net (code "106") (name "Net-(IC20-P$2)") (class "Default")
      (node (ref "C53") (pin "2") (pinfunction "2_2") (pintype "passive"))
      (node (ref "IC20") (pin "2") (pinfunction "P$2_2") (pintype "bidirectional"))
      (node (ref "R64") (pin "2") (pinfunction "2_2") (pintype "passive"))
    )
    (net (code "107") (name "Net-(IC21-EN)") (class "Default")
      (node (ref "IC21") (pin "3") (pinfunction "EN_3") (pintype "bidirectional"))
      (node (ref "R65") (pin "1") (pinfunction "1_1") (pintype "passive"))
    )
    (net (code "108") (name "V+") (class "Default")
      (node (ref "C11") (pin "2") (pinfunction "2_2") (pintype "passive"))
      (node (ref "C12") (pin "1") (pinfunction "1_1") (pintype "passive"))
      (node (ref "C13") (pin "1") (pinfunction "1_1") (pintype "passive"))
      (node (ref "C17") (pin "2") (pinfunction "2_2") (pintype "passive"))
      (node (ref "C18") (pin "2") (pinfunction "2_2") (pintype "passive"))
      (node (ref "C22") (pin "2") (pinfunction "2_2") (pintype "passive"))
      (node (ref "C23") (pin "2") (pinfunction "2_2") (pintype "passive"))
      (node (ref "C38") (pin "2") (pinfunction "2_2") (pintype "passive"))
      (node (ref "C39") (pin "2") (pinfunction "2_2") (pintype "passive"))
      (node (ref "C42") (pin "2") (pinfunction "2_2") (pintype "passive"))
      (node (ref "C43") (pin "2") (pinfunction "2_2") (pintype "passive"))
      (node (ref "C48") (pin "1") (pinfunction "1_1") (pintype "passive"))
      (node (ref "C51") (pin "2") (pinfunction "2_2") (pintype "passive"))
      (node (ref "C58") (pin "1") (pinfunction "1_1") (pintype "passive"))
      (node (ref "C59") (pin "1") (pinfunction "1_1") (pintype "passive"))
      (node (ref "C8") (pin "2") (pinfunction "2_2") (pintype "passive"))
      (node (ref "IC1") (pin "5") (pinfunction "OUT_5") (pintype "bidirectional"))
      (node (ref "IC13") (pin "8") (pinfunction "V+_8") (pintype "power_in"))
      (node (ref "IC14") (pin "8") (pinfunction "V+_8") (pintype "power_in"))
      (node (ref "IC15") (pin "P$8") (pinfunction "V+_P$8") (pintype "bidirectional"))
      (node (ref "IC16") (pin "P$8") (pinfunction "V+_P$8") (pintype "bidirectional"))
      (node (ref "IC18") (pin "4") (pinfunction "V+_4") (pintype "power_in"))
      (node (ref "IC19") (pin "2") (pinfunction "IN_2") (pintype "power_in"))
      (node (ref "IC3") (pin "2") (pinfunction "IN_2") (pintype "power_in"))
      (node (ref "IC4") (pin "4") (pinfunction "V+_4") (pintype "power_in"))
      (node (ref "IC5") (pin "P$8") (pinfunction "V+_P$8") (pintype "bidirectional"))
      (node (ref "IC6") (pin "P$8") (pinfunction "V+_P$8") (pintype "bidirectional"))
      (node (ref "IC7") (pin "8") (pinfunction "V+_8") (pintype "power_in"))
      (node (ref "IC8") (pin "8") (pinfunction "V+_8") (pintype "power_in"))
      (node (ref "JP1") (pin "6") (pinfunction "6_6") (pintype "passive"))
      (node (ref "L1") (pin "1") (pinfunction "1_1") (pintype "passive"))
      (node (ref "L2") (pin "1") (pinfunction "1_1") (pintype "passive"))
      (node (ref "L3") (pin "1") (pinfunction "1_1") (pintype "passive"))
      (node (ref "L4") (pin "1") (pinfunction "1_1") (pintype "passive"))
      (node (ref "R6") (pin "1") (pinfunction "1_1") (pintype "passive"))
    )
    (net (code "109") (name "V-") (class "Default")
      (node (ref "C10") (pin "2") (pinfunction "2_2") (pintype "passive"))
      (node (ref "C15") (pin "2") (pinfunction "2_2") (pintype "passive"))
      (node (ref "C16") (pin "2") (pinfunction "2_2") (pintype "passive"))
      (node (ref "C25") (pin "2") (pinfunction "2_2") (pintype "passive"))
      (node (ref "C26") (pin "2") (pinfunction "2_2") (pintype "passive"))
      (node (ref "C36") (pin "2") (pinfunction "2_2") (pintype "passive"))
      (node (ref "C37") (pin "2") (pinfunction "2_2") (pintype "passive"))
      (node (ref "C40") (pin "2") (pinfunction "2_2") (pintype "passive"))
      (node (ref "C41") (pin "1") (pinfunction "1_1") (pintype "passive"))
      (node (ref "C45") (pin "2") (pinfunction "2_2") (pintype "passive"))
      (node (ref "C46") (pin "2") (pinfunction "2_2") (pintype "passive"))
      (node (ref "C52") (pin "2") (pinfunction "2_2") (pintype "passive"))
      (node (ref "C60") (pin "1") (pinfunction "1_1") (pintype "passive"))
      (node (ref "C61") (pin "1") (pinfunction "1_1") (pintype "passive"))
      (node (ref "IC12") (pin "5") (pinfunction "OUT_5") (pintype "bidirectional"))
      (node (ref "IC13") (pin "4") (pinfunction "V-_4") (pintype "power_in"))
      (node (ref "IC14") (pin "4") (pinfunction "V-_4") (pintype "power_in"))
      (node (ref "IC15") (pin "P$5") (pinfunction "V-_P$5") (pintype "bidirectional"))
      (node (ref "IC16") (pin "P$5") (pinfunction "V-_P$5") (pintype "bidirectional"))
      (node (ref "IC18") (pin "11") (pinfunction "V-_11") (pintype "power_in"))
      (node (ref "IC4") (pin "11") (pinfunction "V-_11") (pintype "power_in"))
      (node (ref "IC5") (pin "P$5") (pinfunction "V-_P$5") (pintype "bidirectional"))
      (node (ref "IC6") (pin "P$5") (pinfunction "V-_P$5") (pintype "bidirectional"))
      (node (ref "IC7") (pin "4") (pinfunction "V-_4") (pintype "power_in"))
      (node (ref "IC8") (pin "4") (pinfunction "V-_4") (pintype "power_in"))
      (node (ref "R50") (pin "1") (pinfunction "1_1") (pintype "passive"))
    )
    (net (code "110") (name "VCCIO") (class "Default")
      (node (ref "C2") (pin "1") (pinfunction "1_1") (pintype "passive"))
      (node (ref "C30") (pin "1") (pinfunction "1_1") (pintype "passive"))
      (node (ref "C50") (pin "1") (pinfunction "1_1") (pintype "passive"))
      (node (ref "C55") (pin "1") (pinfunction "1_1") (pintype "passive"))
      (node (ref "C56") (pin "1") (pinfunction "1_1") (pintype "passive"))
      (node (ref "C57") (pin "1") (pinfunction "1_1") (pintype "passive"))
      (node (ref "IC10") (pin "23") (pinfunction "VDRIVE_23") (pintype "bidirectional"))
      (node (ref "IC10") (pin "34") (pinfunction "REFSELECT_34") (pintype "bidirectional"))
      (node (ref "IC10") (pin "6") (pinfunction "~{PAR}/SER/BYTESEL_6") (pintype "bidirectional"))
      (node (ref "IC10") (pin "7") (pinfunction "~{STBY}_7") (pintype "bidirectional"))
      (node (ref "IC11") (pin "5") (pinfunction "P$5_5") (pintype "bidirectional"))
      (node (ref "IC17") (pin "5") (pinfunction "P$5_5") (pintype "bidirectional"))
      (node (ref "IC2") (pin "5") (pinfunction "~{PR}_5") (pintype "bidirectional"))
      (node (ref "IC2") (pin "6") (pinfunction "VDD_6") (pintype "power_in"))
      (node (ref "IC2") (pin "7") (pinfunction "~{SHDN}_7") (pintype "bidirectional"))
      (node (ref "IC20") (pin "5") (pinfunction "P$5_5") (pintype "bidirectional"))
      (node (ref "IC21") (pin "5") (pinfunction "OUT_5") (pintype "bidirectional"))
      (node (ref "IC22") (pin "5") (pinfunction "~{PR}_5") (pintype "bidirectional"))
      (node (ref "IC22") (pin "6") (pinfunction "VDD_6") (pintype "power_in"))
      (node (ref "IC22") (pin "7") (pinfunction "~{SHDN}_7") (pintype "bidirectional"))
      (node (ref "R1") (pin "2") (pinfunction "2_2") (pintype "passive"))
      (node (ref "R17") (pin "2") (pinfunction "2_2") (pintype "passive"))
      (node (ref "R23") (pin "2") (pinfunction "2_2") (pintype "passive"))
      (node (ref "R27") (pin "2") (pinfunction "2_2") (pintype "passive"))
      (node (ref "R3") (pin "2") (pinfunction "2_2") (pintype "passive"))
      (node (ref "R63") (pin "1") (pinfunction "1_1") (pintype "passive"))
      (node (ref "R8") (pin "2") (pinfunction "2_2") (pintype "passive"))
    )
    (net (code "111") (name "unconnected-(IC2-A1-Pad18)") (class "Default")
      (node (ref "IC2") (pin "18") (pinfunction "A1_18") (pintype "bidirectional"))
    )
    (net (code "112") (name "unconnected-(IC2-A2-Pad19)") (class "Default")
      (node (ref "IC2") (pin "19") (pinfunction "A2_19") (pintype "bidirectional"))
    )
    (net (code "113") (name "unconnected-(IC2-A3-Pad15)") (class "Default")
      (node (ref "IC2") (pin "15") (pinfunction "A3_15") (pintype "bidirectional"))
    )
    (net (code "114") (name "unconnected-(IC2-A4-Pad22)") (class "Default")
      (node (ref "IC2") (pin "22") (pinfunction "A4_22") (pintype "bidirectional"))
    )
    (net (code "115") (name "unconnected-(IC2-NC_1-Pad1)") (class "Default")
      (node (ref "IC2") (pin "1") (pinfunction "NC_1_1") (pintype "bidirectional"))
    )
    (net (code "116") (name "unconnected-(IC2-NC_2-Pad2)") (class "Default")
      (node (ref "IC2") (pin "2") (pinfunction "NC_2_2") (pintype "bidirectional"))
    )
    (net (code "117") (name "unconnected-(IC2-NC_3-Pad12)") (class "Default")
      (node (ref "IC2") (pin "12") (pinfunction "NC_3_12") (pintype "bidirectional"))
    )
    (net (code "118") (name "unconnected-(IC10-BUSY-Pad14)") (class "Default")
      (node (ref "IC10") (pin "14") (pinfunction "BUSY_14") (pintype "bidirectional"))
    )
    (net (code "119") (name "unconnected-(IC10-DB8{slash}DOUTB-Pad25)") (class "Default")
      (node (ref "IC10") (pin "25") (pinfunction "DB8/DOUTB_25") (pintype "bidirectional"))
    )
    (net (code "120") (name "unconnected-(IC10-FRSTDATA-Pad15)") (class "Default")
      (node (ref "IC10") (pin "15") (pinfunction "FRSTDATA_15") (pintype "bidirectional"))
    )
    (net (code "121") (name "unconnected-(IC21-N{slash}C-Pad4)") (class "Default")
      (node (ref "IC21") (pin "4") (pinfunction "N/C_4") (pintype "bidirectional"))
    )
    (net (code "122") (name "unconnected-(IC22-A1-Pad18)") (class "Default")
      (node (ref "IC22") (pin "18") (pinfunction "A1_18") (pintype "bidirectional"))
    )
    (net (code "123") (name "unconnected-(IC22-A2-Pad19)") (class "Default")
      (node (ref "IC22") (pin "19") (pinfunction "A2_19") (pintype "bidirectional"))
    )
    (net (code "124") (name "unconnected-(IC22-A3-Pad15)") (class "Default")
      (node (ref "IC22") (pin "15") (pinfunction "A3_15") (pintype "bidirectional"))
    )
    (net (code "125") (name "unconnected-(IC22-A4-Pad22)") (class "Default")
      (node (ref "IC22") (pin "22") (pinfunction "A4_22") (pintype "bidirectional"))
    )
    (net (code "126") (name "unconnected-(IC22-NC_1-Pad1)") (class "Default")
      (node (ref "IC22") (pin "1") (pinfunction "NC_1_1") (pintype "bidirectional"))
    )
    (net (code "127") (name "unconnected-(IC22-NC_2-Pad2)") (class "Default")
      (node (ref "IC22") (pin "2") (pinfunction "NC_2_2") (pintype "bidirectional"))
    )
    (net (code "128") (name "unconnected-(IC22-NC_3-Pad12)") (class "Default")
      (node (ref "IC22") (pin "12") (pinfunction "NC_3_12") (pintype "bidirectional"))
    )
    (net (code "129") (name "unconnected-(IC22-SDO-Pad10)") (class "Default")
      (node (ref "IC22") (pin "10") (pinfunction "SDO_10") (pintype "bidirectional"))
    )
  )
)
